# MSSRP-Temperature_System_beta.net
KiCad netlist of a schematic drawn in EAGLE
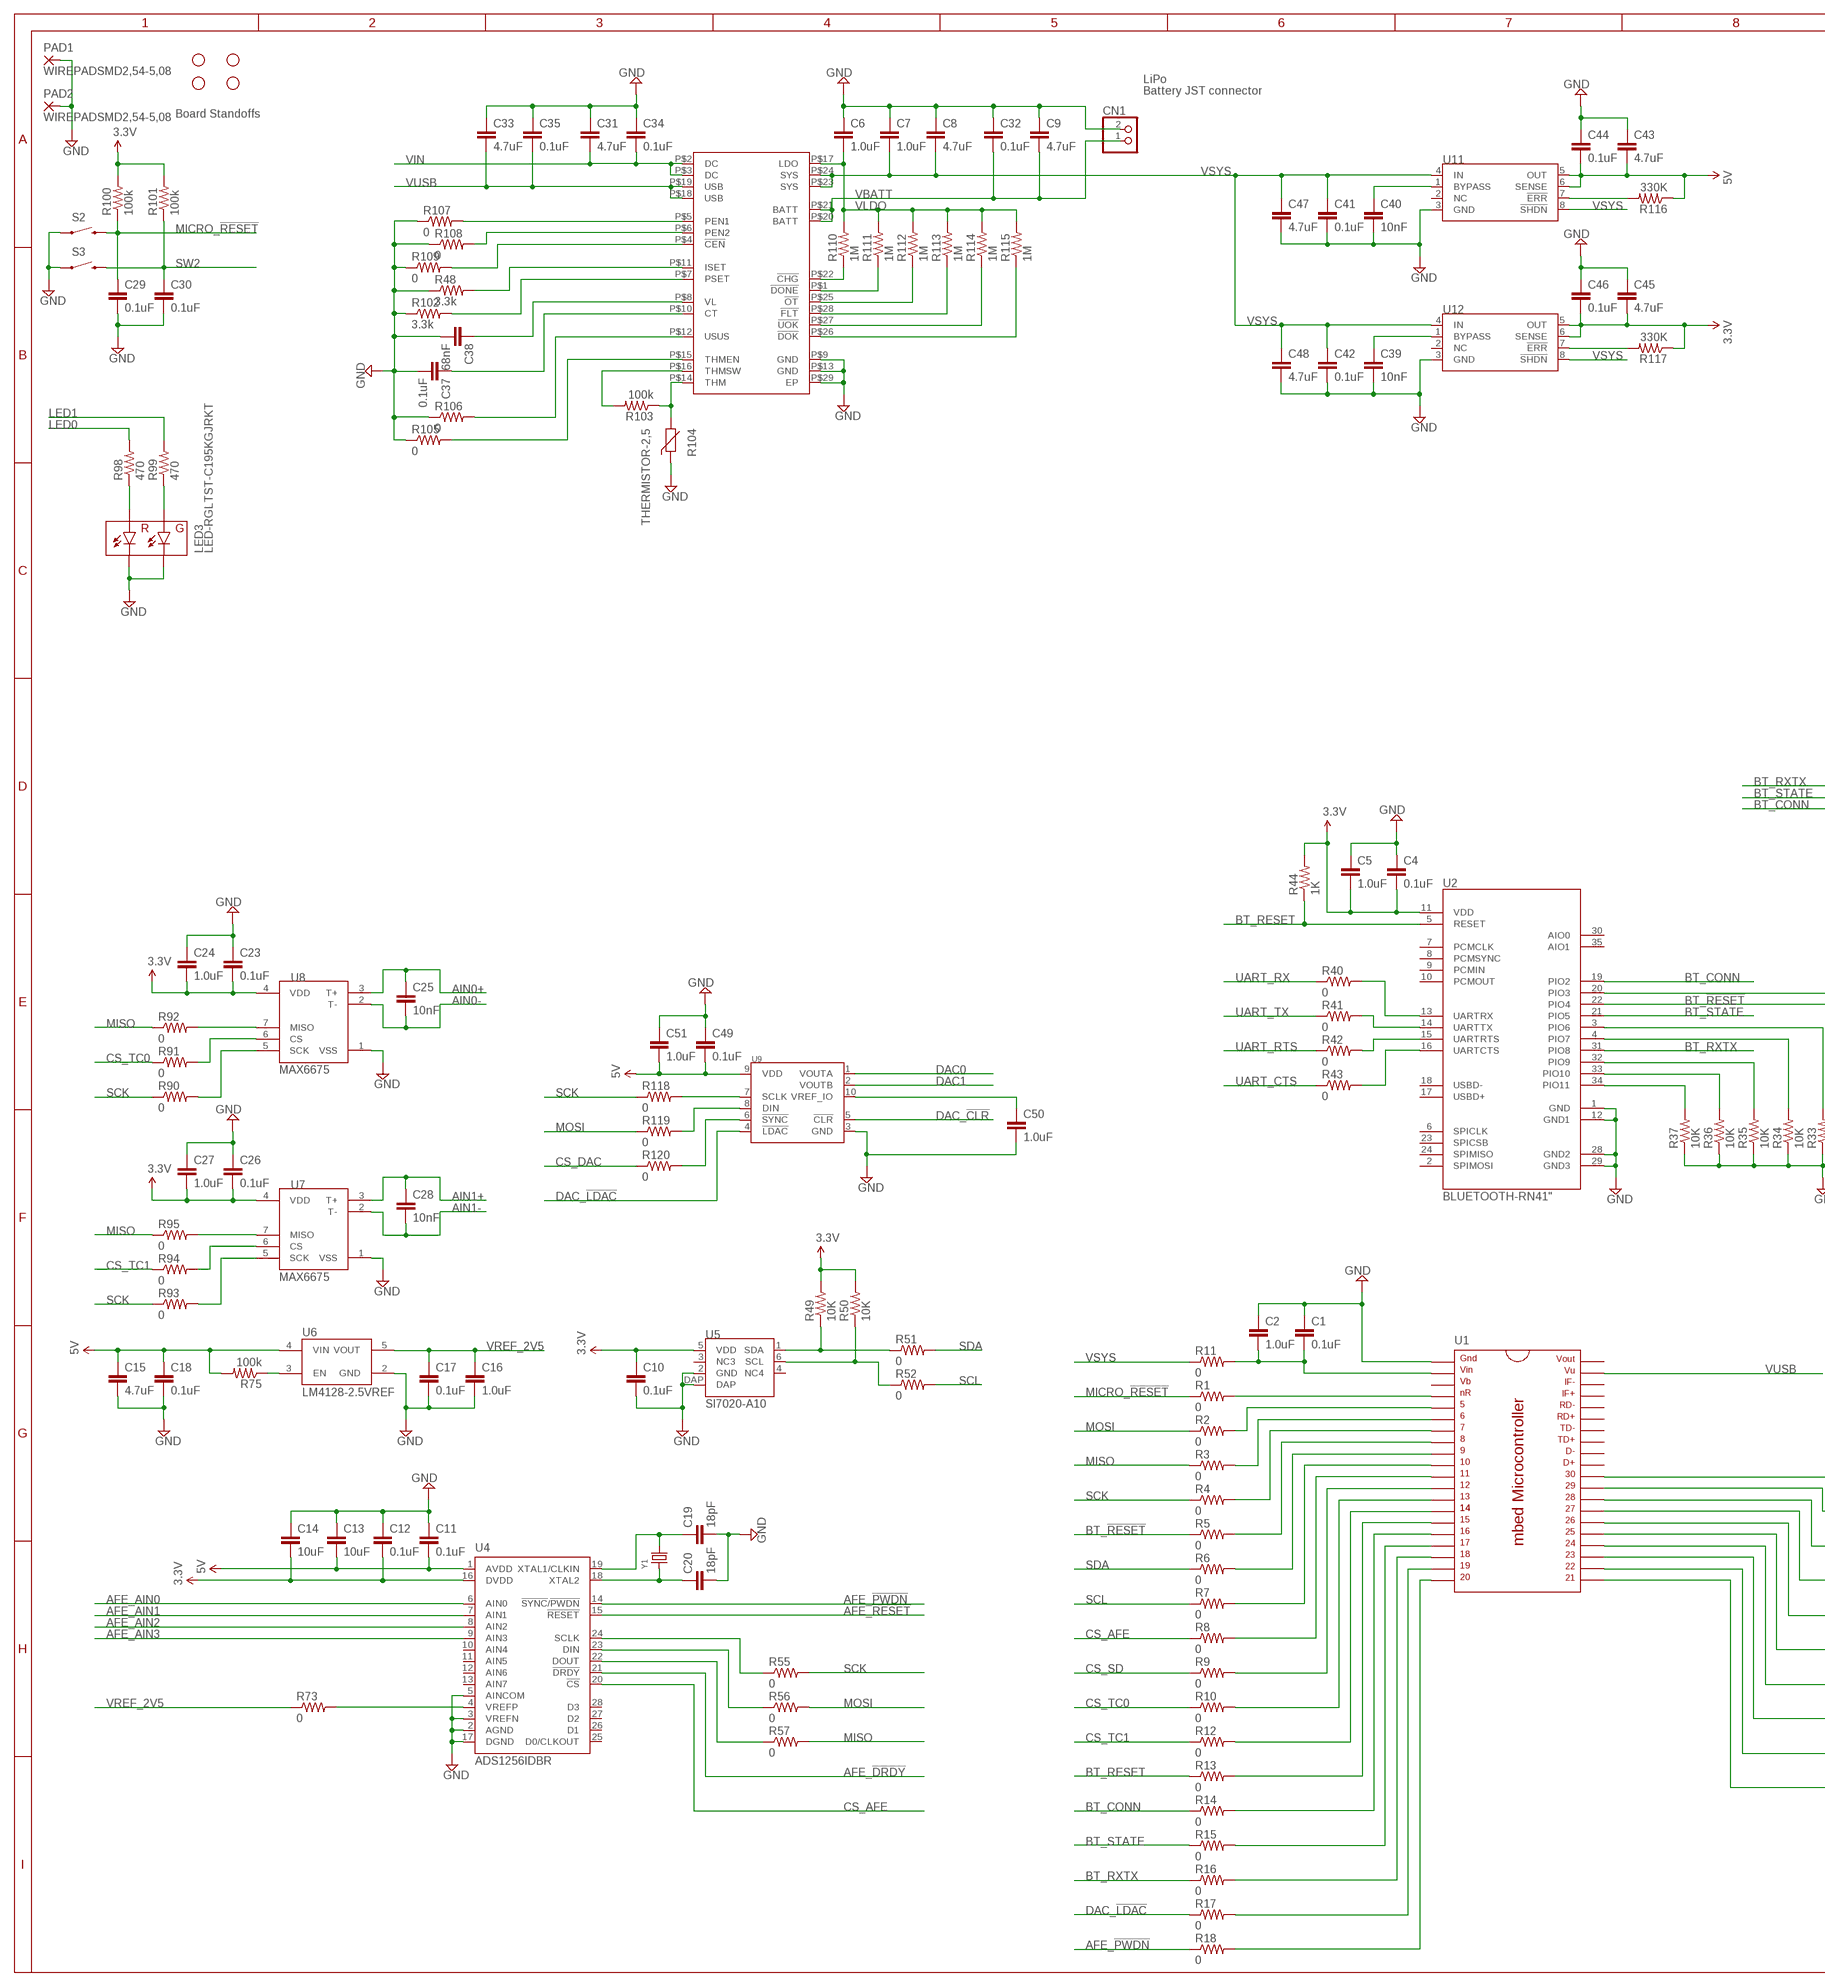
[diagram p0: schematic, sheet 1, part 1 of 2]
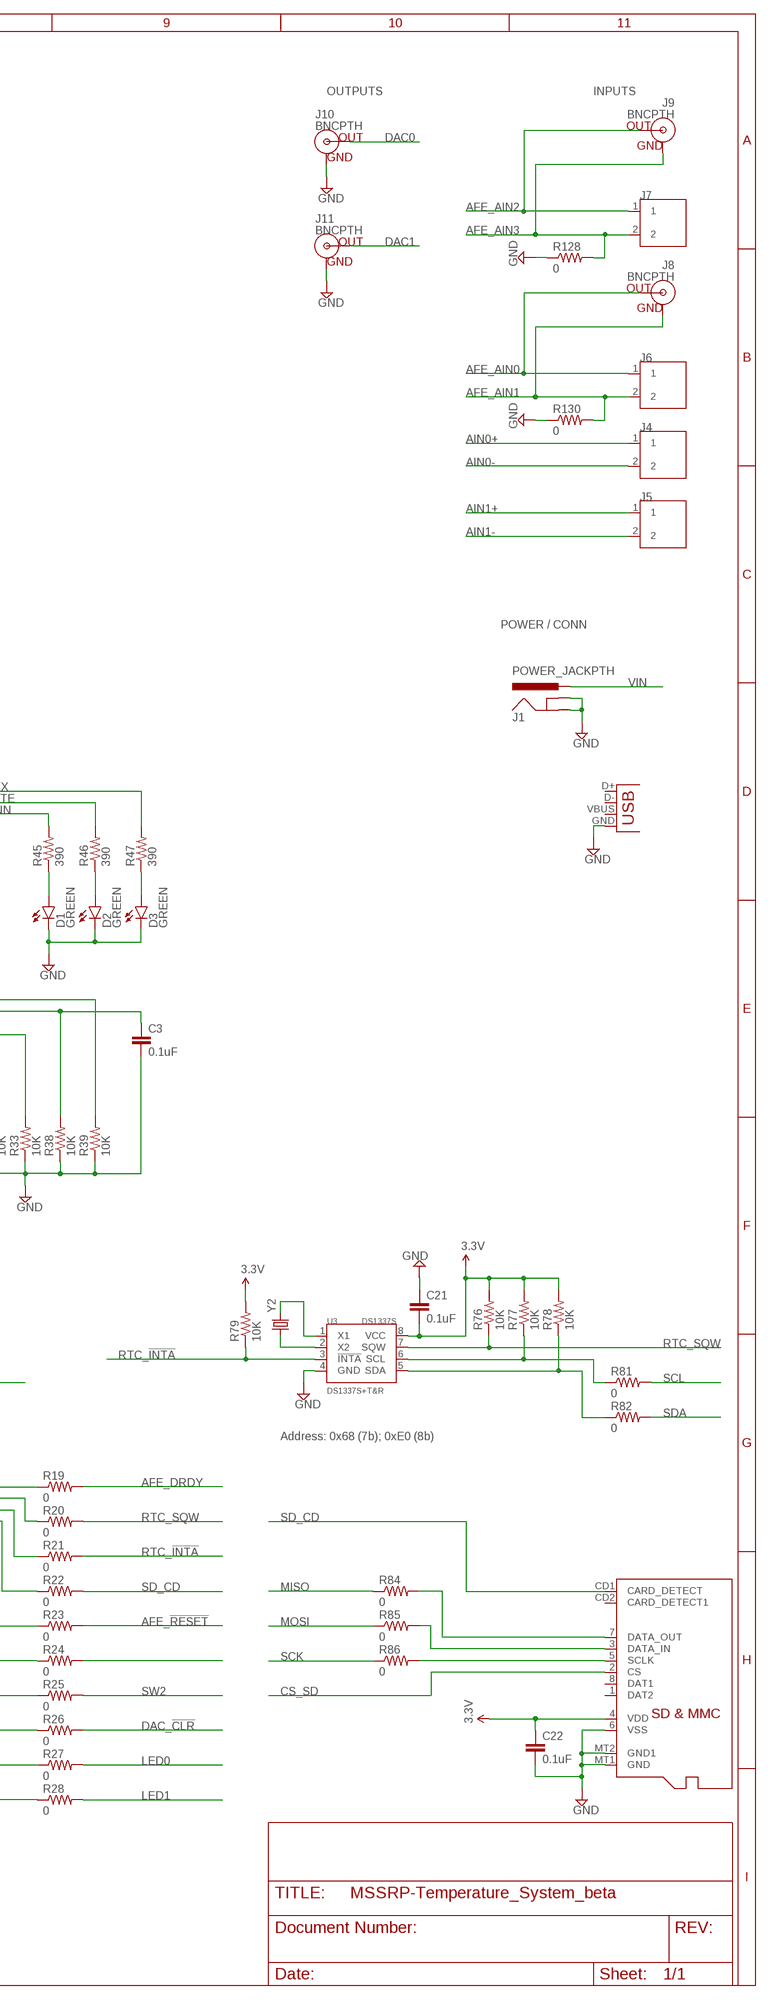
[diagram p1: schematic, sheet 1, part 2 of 2]

(export (version "E")
  (design (tool "Eeschema 10.0.6"))
  (components
    (comp (ref "C1")
      (value "0.1uF")
      (footprint "eagle-import:0603-CAP")
      (libsource (lib "eagle-import") (part "0.1UF-25V-5%(0603)"))
    )
    (comp (ref "C2")
      (value "1.0uF")
      (footprint "eagle-import:0603-CAP")
      (libsource (lib "eagle-import") (part "1.0UF-16V-10%(0603)"))
    )
    (comp (ref "C3")
      (value "0.1uF")
      (footprint "eagle-import:0603-CAP")
      (libsource (lib "eagle-import") (part "0.1UF-25V-5%(0603)"))
    )
    (comp (ref "C4")
      (value "0.1uF")
      (footprint "eagle-import:0603-CAP")
      (libsource (lib "eagle-import") (part "0.1UF-25V-5%(0603)"))
    )
    (comp (ref "C5")
      (value "1.0uF")
      (footprint "eagle-import:0603-CAP")
      (libsource (lib "eagle-import") (part "1.0UF-16V-10%(0603)"))
    )
    (comp (ref "C6")
      (value "1.0uF")
      (footprint "eagle-import:0603-CAP")
      (libsource (lib "eagle-import") (part "1.0UF-16V-10%(0603)"))
    )
    (comp (ref "C7")
      (value "1.0uF")
      (footprint "eagle-import:0603-CAP")
      (libsource (lib "eagle-import") (part "1.0UF-16V-10%(0603)"))
    )
    (comp (ref "C8")
      (value "4.7uF")
      (footprint "eagle-import:0603-CAP")
      (libsource (lib "eagle-import") (part "4.7UF-6.3V-10%(0603)0603"))
    )
    (comp (ref "C9")
      (value "4.7uF")
      (footprint "eagle-import:0603-CAP")
      (libsource (lib "eagle-import") (part "4.7UF-6.3V-10%(0603)0603"))
    )
    (comp (ref "C10")
      (value "0.1uF")
      (footprint "eagle-import:0603-CAP")
      (libsource (lib "eagle-import") (part "0.1UF-25V-5%(0603)"))
    )
    (comp (ref "C11")
      (value "0.1uF")
      (footprint "eagle-import:0603-CAP")
      (libsource (lib "eagle-import") (part "0.1UF-25V-5%(0603)"))
    )
    (comp (ref "C12")
      (value "0.1uF")
      (footprint "eagle-import:0603-CAP")
      (libsource (lib "eagle-import") (part "0.1UF-25V-5%(0603)"))
    )
    (comp (ref "C13")
      (value "10uF")
      (footprint "eagle-import:0603-CAP")
      (libsource (lib "eagle-import") (part "10UF-6.3V-20%(0603)"))
    )
    (comp (ref "C14")
      (value "10uF")
      (footprint "eagle-import:0603-CAP")
      (libsource (lib "eagle-import") (part "10UF-6.3V-20%(0603)"))
    )
    (comp (ref "C15")
      (value "4.7uF")
      (footprint "eagle-import:0603-CAP")
      (libsource (lib "eagle-import") (part "4.7UF-6.3V-10%(0603)0603"))
    )
    (comp (ref "C16")
      (value "1.0uF")
      (footprint "eagle-import:0603-CAP")
      (libsource (lib "eagle-import") (part "1.0UF-16V-10%(0603)"))
    )
    (comp (ref "C17")
      (value "0.1uF")
      (footprint "eagle-import:0603-CAP")
      (libsource (lib "eagle-import") (part "0.1UF-25V-5%(0603)"))
    )
    (comp (ref "C18")
      (value "0.1uF")
      (footprint "eagle-import:0603-CAP")
      (libsource (lib "eagle-import") (part "0.1UF-25V-5%(0603)"))
    )
    (comp (ref "C19")
      (value "18pF")
      (footprint "eagle-import:0603-CAP")
      (libsource (lib "eagle-import") (part "18PF-50V-5%(0603)"))
    )
    (comp (ref "C20")
      (value "18pF")
      (footprint "eagle-import:0603-CAP")
      (libsource (lib "eagle-import") (part "18PF-50V-5%(0603)"))
    )
    (comp (ref "C21")
      (value "0.1uF")
      (footprint "eagle-import:0603-CAP")
      (libsource (lib "eagle-import") (part "0.1UF-25V-5%(0603)"))
    )
    (comp (ref "C22")
      (value "0.1uF")
      (footprint "eagle-import:0603-CAP")
      (libsource (lib "eagle-import") (part "0.1UF-25V-5%(0603)"))
    )
    (comp (ref "C23")
      (value "0.1uF")
      (footprint "eagle-import:0603-CAP")
      (libsource (lib "eagle-import") (part "0.1UF-25V-5%(0603)"))
    )
    (comp (ref "C24")
      (value "1.0uF")
      (footprint "eagle-import:0603-CAP")
      (libsource (lib "eagle-import") (part "1.0UF-16V-10%(0603)"))
    )
    (comp (ref "C25")
      (value "10nF")
      (footprint "eagle-import:0603-CAP")
      (libsource (lib "eagle-import") (part "10NF/10000PF-50V-10%(0603)"))
    )
    (comp (ref "C26")
      (value "0.1uF")
      (footprint "eagle-import:0603-CAP")
      (libsource (lib "eagle-import") (part "0.1UF-25V-5%(0603)"))
    )
    (comp (ref "C27")
      (value "1.0uF")
      (footprint "eagle-import:0603-CAP")
      (libsource (lib "eagle-import") (part "1.0UF-16V-10%(0603)"))
    )
    (comp (ref "C28")
      (value "10nF")
      (footprint "eagle-import:0603-CAP")
      (libsource (lib "eagle-import") (part "10NF/10000PF-50V-10%(0603)"))
    )
    (comp (ref "C29")
      (value "0.1uF")
      (footprint "eagle-import:0603-CAP")
      (libsource (lib "eagle-import") (part "0.1UF-25V-5%(0603)"))
    )
    (comp (ref "C30")
      (value "0.1uF")
      (footprint "eagle-import:0603-CAP")
      (libsource (lib "eagle-import") (part "0.1UF-25V-5%(0603)"))
    )
    (comp (ref "C31")
      (value "4.7uF")
      (footprint "eagle-import:0603-CAP")
      (libsource (lib "eagle-import") (part "4.7UF-6.3V-10%(0603)0603"))
    )
    (comp (ref "C32")
      (value "0.1uF")
      (footprint "eagle-import:0603-CAP")
      (libsource (lib "eagle-import") (part "0.1UF-25V-5%(0603)"))
    )
    (comp (ref "C33")
      (value "4.7uF")
      (footprint "eagle-import:0603-CAP")
      (libsource (lib "eagle-import") (part "4.7UF-6.3V-10%(0603)0603"))
    )
    (comp (ref "C34")
      (value "0.1uF")
      (footprint "eagle-import:0603-CAP")
      (libsource (lib "eagle-import") (part "0.1UF-25V-5%(0603)"))
    )
    (comp (ref "C35")
      (value "0.1uF")
      (footprint "eagle-import:0603-CAP")
      (libsource (lib "eagle-import") (part "0.1UF-25V-5%(0603)"))
    )
    (comp (ref "C37")
      (value "0.1uF")
      (footprint "eagle-import:0603-CAP")
      (libsource (lib "eagle-import") (part "0.1UF-25V-5%(0603)"))
    )
    (comp (ref "C38")
      (value "68nF")
      (footprint "eagle-import:0603-CAP")
      (libsource (lib "eagle-import") (part "0.1UF-25V-5%(0603)"))
    )
    (comp (ref "C39")
      (value "10nF")
      (footprint "eagle-import:0603-CAP")
      (libsource (lib "eagle-import") (part "10NF/10000PF-50V-10%(0603)"))
    )
    (comp (ref "C40")
      (value "10nF")
      (footprint "eagle-import:0603-CAP")
      (libsource (lib "eagle-import") (part "10NF/10000PF-50V-10%(0603)"))
    )
    (comp (ref "C41")
      (value "0.1uF")
      (footprint "eagle-import:0603-CAP")
      (libsource (lib "eagle-import") (part "0.1UF-25V-5%(0603)"))
    )
    (comp (ref "C42")
      (value "0.1uF")
      (footprint "eagle-import:0603-CAP")
      (libsource (lib "eagle-import") (part "0.1UF-25V-5%(0603)"))
    )
    (comp (ref "C43")
      (value "4.7uF")
      (footprint "eagle-import:0603-CAP")
      (libsource (lib "eagle-import") (part "4.7UF-6.3V-10%(0603)0603"))
    )
    (comp (ref "C44")
      (value "0.1uF")
      (footprint "eagle-import:0603-CAP")
      (libsource (lib "eagle-import") (part "0.1UF-25V-5%(0603)"))
    )
    (comp (ref "C45")
      (value "4.7uF")
      (footprint "eagle-import:0603-CAP")
      (libsource (lib "eagle-import") (part "4.7UF-6.3V-10%(0603)0603"))
    )
    (comp (ref "C46")
      (value "0.1uF")
      (footprint "eagle-import:0603-CAP")
      (libsource (lib "eagle-import") (part "0.1UF-25V-5%(0603)"))
    )
    (comp (ref "C47")
      (value "4.7uF")
      (footprint "eagle-import:0603-CAP")
      (libsource (lib "eagle-import") (part "4.7UF-6.3V-10%(0603)0603"))
    )
    (comp (ref "C48")
      (value "4.7uF")
      (footprint "eagle-import:0603-CAP")
      (libsource (lib "eagle-import") (part "4.7UF-6.3V-10%(0603)0603"))
    )
    (comp (ref "C49")
      (value "0.1uF")
      (footprint "eagle-import:0603-CAP")
      (libsource (lib "eagle-import") (part "0.1UF-25V-5%(0603)"))
    )
    (comp (ref "C50")
      (value "1.0uF")
      (footprint "eagle-import:0603-CAP")
      (libsource (lib "eagle-import") (part "1.0UF-16V-10%(0603)"))
    )
    (comp (ref "C51")
      (value "1.0uF")
      (footprint "eagle-import:0603-CAP")
      (libsource (lib "eagle-import") (part "1.0UF-16V-10%(0603)"))
    )
    (comp (ref "CN1")
      (value "JST_2PIN-THM-RA")
      (footprint "eagle-import:JST-PH-2-THM-RA")
      (libsource (lib "eagle-import") (part "JST_2PIN-THM-RA"))
    )
    (comp (ref "D1")
      (value "GREEN")
      (footprint "eagle-import:LED-0603")
      (libsource (lib "eagle-import") (part "LED-GREEN0603"))
    )
    (comp (ref "D2")
      (value "GREEN")
      (footprint "eagle-import:LED-0603")
      (libsource (lib "eagle-import") (part "LED-GREEN0603"))
    )
    (comp (ref "D3")
      (value "GREEN")
      (footprint "eagle-import:LED-0603")
      (libsource (lib "eagle-import") (part "LED-GREEN0603"))
    )
    (comp (ref "J1")
      (value "POWER_JACKPTH")
      (footprint "eagle-import:POWER_JACK_PTH")
      (libsource (lib "eagle-import") (part "POWER_JACKPTH"))
    )
    (comp (ref "J2")
      (value "USBSMD")
      (footprint "eagle-import:USB-MINIB")
      (libsource (lib "eagle-import") (part "USBSMD"))
    )
    (comp (ref "J4")
      (value "TE-2-TERMBLOCK")
      (footprint "eagle-import:TE-2-TERMBLOCK")
      (libsource (lib "eagle-import") (part "TE-2-TERMBLOCK"))
    )
    (comp (ref "J5")
      (value "TE-2-TERMBLOCK")
      (footprint "eagle-import:TE-2-TERMBLOCK")
      (libsource (lib "eagle-import") (part "TE-2-TERMBLOCK"))
    )
    (comp (ref "J6")
      (value "TE-2-TERMBLOCK")
      (footprint "eagle-import:TE-2-TERMBLOCK")
      (libsource (lib "eagle-import") (part "TE-2-TERMBLOCK"))
    )
    (comp (ref "J7")
      (value "TE-2-TERMBLOCK")
      (footprint "eagle-import:TE-2-TERMBLOCK")
      (libsource (lib "eagle-import") (part "TE-2-TERMBLOCK"))
    )
    (comp (ref "J8")
      (value "BNCPTH")
      (footprint "eagle-import:BNC")
      (libsource (lib "eagle-import") (part "BNCPTH"))
    )
    (comp (ref "J9")
      (value "BNCPTH")
      (footprint "eagle-import:BNC")
      (libsource (lib "eagle-import") (part "BNCPTH"))
    )
    (comp (ref "J10")
      (value "BNCPTH")
      (footprint "eagle-import:BNC")
      (libsource (lib "eagle-import") (part "BNCPTH"))
    )
    (comp (ref "J11")
      (value "BNCPTH")
      (footprint "eagle-import:BNC")
      (libsource (lib "eagle-import") (part "BNCPTH"))
    )
    (comp (ref "LED3")
      (value "LED-RGLTST-C195KGJRKT")
      (footprint "eagle-import:LTST-C195KGJRKT")
      (libsource (lib "eagle-import") (part "LED-RGLTST-C195KGJRKT"))
    )
    (comp (ref "PAD1")
      (value "WIREPADSMD2,54-5,08")
      (footprint "eagle-import:SMD2,54-5,08")
      (libsource (lib "eagle-import") (part "WIREPADSMD2,54-5,08"))
    )
    (comp (ref "PAD2")
      (value "WIREPADSMD2,54-5,08")
      (footprint "eagle-import:SMD2,54-5,08")
      (libsource (lib "eagle-import") (part "WIREPADSMD2,54-5,08"))
    )
    (comp (ref "R1")
      (value "0")
      (footprint "eagle-import:0603")
      (libsource (lib "eagle-import") (part "0OHM1/10W5%(0603)"))
    )
    (comp (ref "R2")
      (value "0")
      (footprint "eagle-import:0603")
      (libsource (lib "eagle-import") (part "0OHM1/10W5%(0603)"))
    )
    (comp (ref "R3")
      (value "0")
      (footprint "eagle-import:0603")
      (libsource (lib "eagle-import") (part "0OHM1/10W5%(0603)"))
    )
    (comp (ref "R4")
      (value "0")
      (footprint "eagle-import:0603")
      (libsource (lib "eagle-import") (part "0OHM1/10W5%(0603)"))
    )
    (comp (ref "R5")
      (value "0")
      (footprint "eagle-import:0603")
      (libsource (lib "eagle-import") (part "0OHM1/10W5%(0603)"))
    )
    (comp (ref "R6")
      (value "0")
      (footprint "eagle-import:0603")
      (libsource (lib "eagle-import") (part "0OHM1/10W5%(0603)"))
    )
    (comp (ref "R7")
      (value "0")
      (footprint "eagle-import:0603")
      (libsource (lib "eagle-import") (part "0OHM1/10W5%(0603)"))
    )
    (comp (ref "R8")
      (value "0")
      (footprint "eagle-import:0603")
      (libsource (lib "eagle-import") (part "0OHM1/10W5%(0603)"))
    )
    (comp (ref "R9")
      (value "0")
      (footprint "eagle-import:0603")
      (libsource (lib "eagle-import") (part "0OHM1/10W5%(0603)"))
    )
    (comp (ref "R10")
      (value "0")
      (footprint "eagle-import:0603")
      (libsource (lib "eagle-import") (part "0OHM1/10W5%(0603)"))
    )
    (comp (ref "R11")
      (value "0")
      (footprint "eagle-import:0603")
      (libsource (lib "eagle-import") (part "0OHM1/10W5%(0603)"))
    )
    (comp (ref "R12")
      (value "0")
      (footprint "eagle-import:0603")
      (libsource (lib "eagle-import") (part "0OHM1/10W5%(0603)"))
    )
    (comp (ref "R13")
      (value "0")
      (footprint "eagle-import:0603")
      (libsource (lib "eagle-import") (part "0OHM1/10W5%(0603)"))
    )
    (comp (ref "R14")
      (value "0")
      (footprint "eagle-import:0603")
      (libsource (lib "eagle-import") (part "0OHM1/10W5%(0603)"))
    )
    (comp (ref "R15")
      (value "0")
      (footprint "eagle-import:0603")
      (libsource (lib "eagle-import") (part "0OHM1/10W5%(0603)"))
    )
    (comp (ref "R16")
      (value "0")
      (footprint "eagle-import:0603")
      (libsource (lib "eagle-import") (part "0OHM1/10W5%(0603)"))
    )
    (comp (ref "R17")
      (value "0")
      (footprint "eagle-import:0603")
      (libsource (lib "eagle-import") (part "0OHM1/10W5%(0603)"))
    )
    (comp (ref "R18")
      (value "0")
      (footprint "eagle-import:0603")
      (libsource (lib "eagle-import") (part "0OHM1/10W5%(0603)"))
    )
    (comp (ref "R19")
      (value "0")
      (footprint "eagle-import:0603")
      (libsource (lib "eagle-import") (part "0OHM1/10W5%(0603)"))
    )
    (comp (ref "R20")
      (value "0")
      (footprint "eagle-import:0603")
      (libsource (lib "eagle-import") (part "0OHM1/10W5%(0603)"))
    )
    (comp (ref "R21")
      (value "0")
      (footprint "eagle-import:0603")
      (libsource (lib "eagle-import") (part "0OHM1/10W5%(0603)"))
    )
    (comp (ref "R22")
      (value "0")
      (footprint "eagle-import:0603")
      (libsource (lib "eagle-import") (part "0OHM1/10W5%(0603)"))
    )
    (comp (ref "R23")
      (value "0")
      (footprint "eagle-import:0603")
      (libsource (lib "eagle-import") (part "0OHM1/10W5%(0603)"))
    )
    (comp (ref "R24")
      (value "0")
      (footprint "eagle-import:0603")
      (libsource (lib "eagle-import") (part "0OHM1/10W5%(0603)"))
    )
    (comp (ref "R25")
      (value "0")
      (footprint "eagle-import:0603")
      (libsource (lib "eagle-import") (part "0OHM1/10W5%(0603)"))
    )
    (comp (ref "R26")
      (value "0")
      (footprint "eagle-import:0603")
      (libsource (lib "eagle-import") (part "0OHM1/10W5%(0603)"))
    )
    (comp (ref "R27")
      (value "0")
      (footprint "eagle-import:0603")
      (libsource (lib "eagle-import") (part "0OHM1/10W5%(0603)"))
    )
    (comp (ref "R28")
      (value "0")
      (footprint "eagle-import:0603")
      (libsource (lib "eagle-import") (part "0OHM1/10W5%(0603)"))
    )
    (comp (ref "R33")
      (value "10K")
      (footprint "eagle-import:0603-RES")
      (libsource (lib "eagle-import") (part "10KOHM1/10W1%(0603)0603"))
    )
    (comp (ref "R34")
      (value "10K")
      (footprint "eagle-import:0603-RES")
      (libsource (lib "eagle-import") (part "10KOHM1/10W1%(0603)0603"))
    )
    (comp (ref "R35")
      (value "10K")
      (footprint "eagle-import:0603-RES")
      (libsource (lib "eagle-import") (part "10KOHM1/10W1%(0603)0603"))
    )
    (comp (ref "R36")
      (value "10K")
      (footprint "eagle-import:0603-RES")
      (libsource (lib "eagle-import") (part "10KOHM1/10W1%(0603)0603"))
    )
    (comp (ref "R37")
      (value "10K")
      (footprint "eagle-import:0603-RES")
      (libsource (lib "eagle-import") (part "10KOHM1/10W1%(0603)0603"))
    )
    (comp (ref "R38")
      (value "10K")
      (footprint "eagle-import:0603-RES")
      (libsource (lib "eagle-import") (part "10KOHM1/10W1%(0603)0603"))
    )
    (comp (ref "R39")
      (value "10K")
      (footprint "eagle-import:0603-RES")
      (libsource (lib "eagle-import") (part "10KOHM1/10W1%(0603)0603"))
    )
    (comp (ref "R40")
      (value "0")
      (footprint "eagle-import:0603")
      (libsource (lib "eagle-import") (part "0OHM1/10W5%(0603)"))
    )
    (comp (ref "R41")
      (value "0")
      (footprint "eagle-import:0603")
      (libsource (lib "eagle-import") (part "0OHM1/10W5%(0603)"))
    )
    (comp (ref "R42")
      (value "0")
      (footprint "eagle-import:0603")
      (libsource (lib "eagle-import") (part "0OHM1/10W5%(0603)"))
    )
    (comp (ref "R43")
      (value "0")
      (footprint "eagle-import:0603")
      (libsource (lib "eagle-import") (part "0OHM1/10W5%(0603)"))
    )
    (comp (ref "R44")
      (value "1K")
      (footprint "eagle-import:0603-RES")
      (libsource (lib "eagle-import") (part "1KOHM1/10W1%(0603)"))
    )
    (comp (ref "R45")
      (value "390")
      (footprint "eagle-import:0603-RES")
      (libsource (lib "eagle-import") (part "390OHM1/10W1%(0603)"))
    )
    (comp (ref "R46")
      (value "390")
      (footprint "eagle-import:0603-RES")
      (libsource (lib "eagle-import") (part "390OHM1/10W1%(0603)"))
    )
    (comp (ref "R47")
      (value "390")
      (footprint "eagle-import:0603-RES")
      (libsource (lib "eagle-import") (part "390OHM1/10W1%(0603)"))
    )
    (comp (ref "R48")
      (value "3.3k")
      (footprint "eagle-import:0603-RES")
      (libsource (lib "eagle-import") (part "3.3MOHM-1/10W-1%(0603)"))
    )
    (comp (ref "R49")
      (value "10K")
      (footprint "eagle-import:0603-RES")
      (libsource (lib "eagle-import") (part "10KOHM1/10W1%(0603)0603"))
    )
    (comp (ref "R50")
      (value "10K")
      (footprint "eagle-import:0603-RES")
      (libsource (lib "eagle-import") (part "10KOHM1/10W1%(0603)0603"))
    )
    (comp (ref "R51")
      (value "0")
      (footprint "eagle-import:0603")
      (libsource (lib "eagle-import") (part "0OHM1/10W5%(0603)"))
    )
    (comp (ref "R52")
      (value "0")
      (footprint "eagle-import:0603")
      (libsource (lib "eagle-import") (part "0OHM1/10W5%(0603)"))
    )
    (comp (ref "R55")
      (value "0")
      (footprint "eagle-import:0603")
      (libsource (lib "eagle-import") (part "0OHM1/10W5%(0603)"))
    )
    (comp (ref "R56")
      (value "0")
      (footprint "eagle-import:0603")
      (libsource (lib "eagle-import") (part "0OHM1/10W5%(0603)"))
    )
    (comp (ref "R57")
      (value "0")
      (footprint "eagle-import:0603")
      (libsource (lib "eagle-import") (part "0OHM1/10W5%(0603)"))
    )
    (comp (ref "R73")
      (value "0")
      (footprint "eagle-import:0603")
      (libsource (lib "eagle-import") (part "0OHM1/10W5%(0603)"))
    )
    (comp (ref "R75")
      (value "100k")
      (footprint "eagle-import:0603-RES")
      (libsource (lib "eagle-import") (part "100KOHM1/10W1%(0603)"))
    )
    (comp (ref "R76")
      (value "10K")
      (footprint "eagle-import:0603-RES")
      (libsource (lib "eagle-import") (part "10KOHM1/10W1%(0603)0603"))
    )
    (comp (ref "R77")
      (value "10K")
      (footprint "eagle-import:0603-RES")
      (libsource (lib "eagle-import") (part "10KOHM1/10W1%(0603)0603"))
    )
    (comp (ref "R78")
      (value "10K")
      (footprint "eagle-import:0603-RES")
      (libsource (lib "eagle-import") (part "10KOHM1/10W1%(0603)0603"))
    )
    (comp (ref "R79")
      (value "10K")
      (footprint "eagle-import:0603-RES")
      (libsource (lib "eagle-import") (part "10KOHM1/10W1%(0603)0603"))
    )
    (comp (ref "R81")
      (value "0")
      (footprint "eagle-import:0603")
      (libsource (lib "eagle-import") (part "0OHM1/10W5%(0603)"))
    )
    (comp (ref "R82")
      (value "0")
      (footprint "eagle-import:0603")
      (libsource (lib "eagle-import") (part "0OHM1/10W5%(0603)"))
    )
    (comp (ref "R84")
      (value "0")
      (footprint "eagle-import:0603")
      (libsource (lib "eagle-import") (part "0OHM1/10W5%(0603)"))
    )
    (comp (ref "R85")
      (value "0")
      (footprint "eagle-import:0603")
      (libsource (lib "eagle-import") (part "0OHM1/10W5%(0603)"))
    )
    (comp (ref "R86")
      (value "0")
      (footprint "eagle-import:0603")
      (libsource (lib "eagle-import") (part "0OHM1/10W5%(0603)"))
    )
    (comp (ref "R90")
      (value "0")
      (footprint "eagle-import:0603")
      (libsource (lib "eagle-import") (part "0OHM1/10W5%(0603)"))
    )
    (comp (ref "R91")
      (value "0")
      (footprint "eagle-import:0603")
      (libsource (lib "eagle-import") (part "0OHM1/10W5%(0603)"))
    )
    (comp (ref "R92")
      (value "0")
      (footprint "eagle-import:0603")
      (libsource (lib "eagle-import") (part "0OHM1/10W5%(0603)"))
    )
    (comp (ref "R93")
      (value "0")
      (footprint "eagle-import:0603")
      (libsource (lib "eagle-import") (part "0OHM1/10W5%(0603)"))
    )
    (comp (ref "R94")
      (value "0")
      (footprint "eagle-import:0603")
      (libsource (lib "eagle-import") (part "0OHM1/10W5%(0603)"))
    )
    (comp (ref "R95")
      (value "0")
      (footprint "eagle-import:0603")
      (libsource (lib "eagle-import") (part "0OHM1/10W5%(0603)"))
    )
    (comp (ref "R98")
      (value "470")
      (footprint "eagle-import:0603-RES")
      (libsource (lib "eagle-import") (part "470OHM1/10W1%(0603)"))
    )
    (comp (ref "R99")
      (value "470")
      (footprint "eagle-import:0603-RES")
      (libsource (lib "eagle-import") (part "470OHM1/10W1%(0603)"))
    )
    (comp (ref "R100")
      (value "100k")
      (footprint "eagle-import:0603-RES")
      (libsource (lib "eagle-import") (part "100KOHM1/10W1%(0603)"))
    )
    (comp (ref "R101")
      (value "100k")
      (footprint "eagle-import:0603-RES")
      (libsource (lib "eagle-import") (part "100KOHM1/10W1%(0603)"))
    )
    (comp (ref "R102")
      (value "3.3k")
      (footprint "eagle-import:0603-RES")
      (libsource (lib "eagle-import") (part "3.3MOHM-1/10W-1%(0603)"))
    )
    (comp (ref "R103")
      (value "100k")
      (footprint "eagle-import:0603-RES")
      (libsource (lib "eagle-import") (part "100OHM1/10W1%(0603)"))
    )
    (comp (ref "R104")
      (value "THERMISTOR-2,5")
      (footprint "eagle-import:RS-2,5")
      (libsource (lib "eagle-import") (part "THERMISTOR-2,5"))
    )
    (comp (ref "R105")
      (value "0")
      (footprint "eagle-import:0603")
      (libsource (lib "eagle-import") (part "0OHM1/10W5%(0603)"))
    )
    (comp (ref "R106")
      (value "0")
      (footprint "eagle-import:0603")
      (libsource (lib "eagle-import") (part "0OHM1/10W5%(0603)"))
    )
    (comp (ref "R107")
      (value "0")
      (footprint "eagle-import:0603")
      (libsource (lib "eagle-import") (part "0OHM1/10W5%(0603)"))
    )
    (comp (ref "R108")
      (value "0")
      (footprint "eagle-import:0603")
      (libsource (lib "eagle-import") (part "0OHM1/10W5%(0603)"))
    )
    (comp (ref "R109")
      (value "0")
      (footprint "eagle-import:0603")
      (libsource (lib "eagle-import") (part "0OHM1/10W5%(0603)"))
    )
    (comp (ref "R110")
      (value "1M")
      (footprint "eagle-import:0603-RES")
      (libsource (lib "eagle-import") (part "330KOHM1/10W1%(0603)0603"))
    )
    (comp (ref "R111")
      (value "1M")
      (footprint "eagle-import:0603-RES")
      (libsource (lib "eagle-import") (part "330KOHM1/10W1%(0603)0603"))
    )
    (comp (ref "R112")
      (value "1M")
      (footprint "eagle-import:0603-RES")
      (libsource (lib "eagle-import") (part "330KOHM1/10W1%(0603)0603"))
    )
    (comp (ref "R113")
      (value "1M")
      (footprint "eagle-import:0603-RES")
      (libsource (lib "eagle-import") (part "330KOHM1/10W1%(0603)0603"))
    )
    (comp (ref "R114")
      (value "1M")
      (footprint "eagle-import:0603-RES")
      (libsource (lib "eagle-import") (part "330KOHM1/10W1%(0603)0603"))
    )
    (comp (ref "R115")
      (value "1M")
      (footprint "eagle-import:0603-RES")
      (libsource (lib "eagle-import") (part "330KOHM1/10W1%(0603)0603"))
    )
    (comp (ref "R116")
      (value "330K")
      (footprint "eagle-import:0603-RES")
      (libsource (lib "eagle-import") (part "330KOHM1/10W1%(0603)0603"))
    )
    (comp (ref "R117")
      (value "330K")
      (footprint "eagle-import:0603-RES")
      (libsource (lib "eagle-import") (part "330KOHM1/10W1%(0603)0603"))
    )
    (comp (ref "R118")
      (value "0")
      (footprint "eagle-import:0603")
      (libsource (lib "eagle-import") (part "0OHM1/10W5%(0603)"))
    )
    (comp (ref "R119")
      (value "0")
      (footprint "eagle-import:0603")
      (libsource (lib "eagle-import") (part "0OHM1/10W5%(0603)"))
    )
    (comp (ref "R120")
      (value "0")
      (footprint "eagle-import:0603")
      (libsource (lib "eagle-import") (part "0OHM1/10W5%(0603)"))
    )
    (comp (ref "R128")
      (value "0")
      (footprint "eagle-import:0603")
      (libsource (lib "eagle-import") (part "0OHM1/10W5%(0603)"))
    )
    (comp (ref "R130")
      (value "0")
      (footprint "eagle-import:0603")
      (libsource (lib "eagle-import") (part "0OHM1/10W5%(0603)"))
    )
    (comp (ref "S2")
      (value "SWITCH-MOMENTARY-2-SMD-1101NE")
      (footprint "eagle-import:TACTILE-SWITCH-1101NE")
      (libsource (lib "eagle-import") (part "SWITCH-MOMENTARY-2-SMD-1101NE"))
    )
    (comp (ref "S3")
      (value "SWITCH-MOMENTARY-2-SMD-1101NE")
      (footprint "eagle-import:TACTILE-SWITCH-1101NE")
      (libsource (lib "eagle-import") (part "SWITCH-MOMENTARY-2-SMD-1101NE"))
    )
    (comp (ref "STANDOFF1")
      (value "STAND-OFF")
      (footprint "eagle-import:STAND-OFF")
      (libsource (lib "eagle-import") (part "STAND-OFF"))
    )
    (comp (ref "STANDOFF2")
      (value "STAND-OFF")
      (footprint "eagle-import:STAND-OFF")
      (libsource (lib "eagle-import") (part "STAND-OFF"))
    )
    (comp (ref "STANDOFF3")
      (value "STAND-OFF")
      (footprint "eagle-import:STAND-OFF")
      (libsource (lib "eagle-import") (part "STAND-OFF"))
    )
    (comp (ref "STANDOFF4")
      (value "STAND-OFF")
      (footprint "eagle-import:STAND-OFF")
      (libsource (lib "eagle-import") (part "STAND-OFF"))
    )
    (comp (ref "U$1")
      (value "MICROSD")
      (footprint "eagle-import:MICROSD")
      (libsource (lib "eagle-import") (part "MICROSD"))
    )
    (comp (ref "U1")
      (value "MBED")
      (footprint "eagle-import:DIL40_0.9")
      (libsource (lib "eagle-import") (part "MBED"))
    )
    (comp (ref "U2")
      (value "BLUETOOTH-RN41\"")
      (footprint "eagle-import:RN41")
      (libsource (lib "eagle-import") (part "BLUETOOTH-RN41{dblquote}"))
    )
    (comp (ref "U3")
      (value "DS1337S+T&R")
      (footprint "eagle-import:SOIC8")
      (libsource (lib "eagle-import") (part "DS1337S+T&R"))
    )
    (comp (ref "U4")
      (value "ADS1256IDBR")
      (footprint "eagle-import:SSOP28")
      (libsource (lib "eagle-import") (part "ADS1256IDBR"))
    )
    (comp (ref "U5")
      (value "SI7020-A10")
      (footprint "eagle-import:DFN6")
      (libsource (lib "eagle-import") (part "SI7020-A10"))
    )
    (comp (ref "U6")
      (value "LM4128-2.5VREF")
      (footprint "eagle-import:SOT23-5")
      (libsource (lib "eagle-import") (part "LM4128-2.5VREF"))
    )
    (comp (ref "U7")
      (value "MAX6675")
      (footprint "eagle-import:SO08-MAX6675")
      (libsource (lib "eagle-import") (part "MAX6675"))
    )
    (comp (ref "U8")
      (value "MAX6675")
      (footprint "eagle-import:SO08-MAX6675")
      (libsource (lib "eagle-import") (part "MAX6675"))
    )
    (comp (ref "U9")
      (value "DAC7562")
      (footprint "eagle-import:MSOP10")
      (libsource (lib "eagle-import") (part "DAC7562"))
    )
    (comp (ref "U10")
      (value "MAX8934A")
      (footprint "eagle-import:QFN28")
      (libsource (lib "eagle-import") (part "MAX8934A"))
    )
    (comp (ref "U11")
      (value "LP2989AIM")
      (footprint "eagle-import:SOIC8")
      (libsource (lib "eagle-import") (part "LP2989AIM"))
    )
    (comp (ref "U12")
      (value "LP2989AIM")
      (footprint "eagle-import:SOIC8")
      (libsource (lib "eagle-import") (part "LP2989AIM"))
    )
    (comp (ref "Y1")
      (value "CRYSTALSMD")
      (footprint "eagle-import:HC49UP")
      (libsource (lib "eagle-import") (part "microbuilder_CRYSTALSMD"))
    )
    (comp (ref "Y2")
      (value "CRYSTALSMD")
      (footprint "eagle-import:HC49UP")
      (libsource (lib "eagle-import") (part "CRYSTALSMD"))
    )
  )
  (nets
    (net (code "1") (name "/AFE_AIN0") (class "Default")
      (node (ref "J6") (pin "1") (pinfunction "1_1") (pintype "passive"))
      (node (ref "J8") (pin "S") (pinfunction "OUT_S") (pintype "bidirectional"))
      (node (ref "U4") (pin "6") (pinfunction "AIN0_6") (pintype "input"))
    )
    (net (code "2") (name "/AFE_AIN1") (class "Default")
      (node (ref "J6") (pin "2") (pinfunction "2_2") (pintype "passive"))
      (node (ref "J8") (pin "GND") (pinfunction "GND_GND") (pintype "bidirectional"))
      (node (ref "R130") (pin "2") (pinfunction "2_2") (pintype "passive"))
      (node (ref "U4") (pin "7") (pinfunction "AIN1_7") (pintype "input"))
    )
    (net (code "3") (name "/AFE_AIN2") (class "Default")
      (node (ref "J7") (pin "1") (pinfunction "1_1") (pintype "passive"))
      (node (ref "J9") (pin "S") (pinfunction "OUT_S") (pintype "bidirectional"))
      (node (ref "U4") (pin "8") (pinfunction "AIN2_8") (pintype "input"))
    )
    (net (code "4") (name "/AFE_AIN3") (class "Default")
      (node (ref "J7") (pin "2") (pinfunction "2_2") (pintype "passive"))
      (node (ref "J9") (pin "GND") (pinfunction "GND_GND") (pintype "bidirectional"))
      (node (ref "R128") (pin "2") (pinfunction "2_2") (pintype "passive"))
      (node (ref "U4") (pin "9") (pinfunction "AIN3_9") (pintype "input"))
    )
    (net (code "5") (name "/AFE_DRDY") (class "Default")
      (node (ref "R19") (pin "2") (pinfunction "2_2") (pintype "passive"))
    )
    (net (code "6") (name "/AFE_~{DRDY}") (class "Default")
      (node (ref "U4") (pin "21") (pinfunction "~{DRDY}_21") (pintype "output"))
    )
    (net (code "7") (name "/AFE_~{PWDN}") (class "Default")
      (node (ref "R18") (pin "1") (pinfunction "1_1") (pintype "passive"))
      (node (ref "U4") (pin "14") (pinfunction "~{SYNC}/~{PWDN}_14") (pintype "input"))
    )
    (net (code "8") (name "/AFE_~{RESET}") (class "Default")
      (node (ref "R23") (pin "2") (pinfunction "2_2") (pintype "passive"))
      (node (ref "U4") (pin "15") (pinfunction "~{RESET}_15") (pintype "input"))
    )
    (net (code "9") (name "/AIN0+") (class "Default")
      (node (ref "C25") (pin "1") (pinfunction "1_1") (pintype "passive"))
      (node (ref "J4") (pin "1") (pinfunction "1_1") (pintype "passive"))
      (node (ref "U8") (pin "3") (pinfunction "T+_3") (pintype "bidirectional"))
    )
    (net (code "10") (name "/AIN0-") (class "Default")
      (node (ref "C25") (pin "2") (pinfunction "2_2") (pintype "passive"))
      (node (ref "J4") (pin "2") (pinfunction "2_2") (pintype "passive"))
      (node (ref "U8") (pin "2") (pinfunction "T-_2") (pintype "bidirectional"))
    )
    (net (code "11") (name "/AIN1+") (class "Default")
      (node (ref "C28") (pin "1") (pinfunction "1_1") (pintype "passive"))
      (node (ref "J5") (pin "1") (pinfunction "1_1") (pintype "passive"))
      (node (ref "U7") (pin "3") (pinfunction "T+_3") (pintype "bidirectional"))
    )
    (net (code "12") (name "/AIN1-") (class "Default")
      (node (ref "C28") (pin "2") (pinfunction "2_2") (pintype "passive"))
      (node (ref "J5") (pin "2") (pinfunction "2_2") (pintype "passive"))
      (node (ref "U7") (pin "2") (pinfunction "T-_2") (pintype "bidirectional"))
    )
    (net (code "13") (name "/BT_CONN") (class "Default")
      (node (ref "R14") (pin "1") (pinfunction "1_1") (pintype "passive"))
      (node (ref "R45") (pin "2") (pinfunction "2_2") (pintype "passive"))
      (node (ref "U2") (pin "19") (pinfunction "PIO2_19") (pintype "bidirectional"))
    )
    (net (code "14") (name "/BT_RESET") (class "Default")
      (node (ref "R13") (pin "1") (pinfunction "1_1") (pintype "passive"))
      (node (ref "R44") (pin "1") (pinfunction "1_1") (pintype "passive"))
      (node (ref "U2") (pin "5") (pinfunction "RESET_5") (pintype "bidirectional"))
    )
    (net (code "15") (name "/BT_RXTX") (class "Default")
      (node (ref "R16") (pin "1") (pinfunction "1_1") (pintype "passive"))
      (node (ref "R47") (pin "2") (pinfunction "2_2") (pintype "passive"))
      (node (ref "U2") (pin "31") (pinfunction "PIO8_31") (pintype "bidirectional"))
    )
    (net (code "16") (name "/BT_STATE") (class "Default")
      (node (ref "R15") (pin "1") (pinfunction "1_1") (pintype "passive"))
      (node (ref "R46") (pin "2") (pinfunction "2_2") (pintype "passive"))
      (node (ref "U2") (pin "21") (pinfunction "PIO5_21") (pintype "bidirectional"))
    )
    (net (code "17") (name "/BT_~{RESET}") (class "Default")
      (node (ref "C3") (pin "1") (pinfunction "1_1") (pintype "passive"))
      (node (ref "R38") (pin "2") (pinfunction "2_2") (pintype "passive"))
      (node (ref "R5") (pin "1") (pinfunction "1_1") (pintype "passive"))
      (node (ref "U2") (pin "22") (pinfunction "PIO4_22") (pintype "bidirectional"))
    )
    (net (code "18") (name "/CS_AFE") (class "Default")
      (node (ref "R8") (pin "1") (pinfunction "1_1") (pintype "passive"))
      (node (ref "U4") (pin "20") (pinfunction "~{CS}_20") (pintype "input"))
    )
    (net (code "19") (name "/CS_DAC") (class "Default")
      (node (ref "R120") (pin "1") (pinfunction "1_1") (pintype "passive"))
    )
    (net (code "20") (name "/CS_SD") (class "Default")
      (node (ref "R9") (pin "1") (pinfunction "1_1") (pintype "passive"))
      (node (ref "U$1") (pin "2") (pinfunction "CS_2") (pintype "input"))
    )
    (net (code "21") (name "/CS_TC0") (class "Default")
      (node (ref "R10") (pin "1") (pinfunction "1_1") (pintype "passive"))
      (node (ref "R91") (pin "1") (pinfunction "1_1") (pintype "passive"))
    )
    (net (code "22") (name "/CS_TC1") (class "Default")
      (node (ref "R12") (pin "1") (pinfunction "1_1") (pintype "passive"))
      (node (ref "R94") (pin "1") (pinfunction "1_1") (pintype "passive"))
    )
    (net (code "23") (name "/DAC0") (class "Default")
      (node (ref "J10") (pin "S") (pinfunction "OUT_S") (pintype "bidirectional"))
      (node (ref "U9") (pin "1") (pinfunction "VOUTA_1") (pintype "output"))
    )
    (net (code "24") (name "/DAC1") (class "Default")
      (node (ref "J11") (pin "S") (pinfunction "OUT_S") (pintype "bidirectional"))
      (node (ref "U9") (pin "2") (pinfunction "VOUTB_2") (pintype "output"))
    )
    (net (code "25") (name "/DAC_~{CLR}") (class "Default")
      (node (ref "R26") (pin "2") (pinfunction "2_2") (pintype "passive"))
      (node (ref "U9") (pin "5") (pinfunction "~{CLR}_5") (pintype "input"))
    )
    (net (code "26") (name "/DAC_~{LDAC}") (class "Default")
      (node (ref "R17") (pin "1") (pinfunction "1_1") (pintype "passive"))
      (node (ref "U9") (pin "4") (pinfunction "~{LDAC}_4") (pintype "input"))
    )
    (net (code "27") (name "/LED0") (class "Default")
      (node (ref "R27") (pin "2") (pinfunction "2_2") (pintype "passive"))
      (node (ref "R98") (pin "2") (pinfunction "2_2") (pintype "passive"))
    )
    (net (code "28") (name "/LED1") (class "Default")
      (node (ref "R28") (pin "2") (pinfunction "2_2") (pintype "passive"))
      (node (ref "R99") (pin "2") (pinfunction "2_2") (pintype "passive"))
    )
    (net (code "29") (name "/MICRO_~{RESET}") (class "Default")
      (node (ref "C29") (pin "1") (pinfunction "1_1") (pintype "passive"))
      (node (ref "R1") (pin "1") (pinfunction "1_1") (pintype "passive"))
      (node (ref "R100") (pin "1") (pinfunction "1_1") (pintype "passive"))
      (node (ref "S2") (pin "P$2") (pinfunction "2_P$2") (pintype "passive"))
    )
    (net (code "30") (name "/MISO") (class "Default")
      (node (ref "R3") (pin "1") (pinfunction "1_1") (pintype "passive"))
      (node (ref "R57") (pin "2") (pinfunction "2_2") (pintype "passive"))
      (node (ref "R84") (pin "1") (pinfunction "1_1") (pintype "passive"))
      (node (ref "R92") (pin "1") (pinfunction "1_1") (pintype "passive"))
      (node (ref "R95") (pin "1") (pinfunction "1_1") (pintype "passive"))
    )
    (net (code "31") (name "/MOSI") (class "Default")
      (node (ref "R119") (pin "1") (pinfunction "1_1") (pintype "passive"))
      (node (ref "R2") (pin "1") (pinfunction "1_1") (pintype "passive"))
      (node (ref "R56") (pin "2") (pinfunction "2_2") (pintype "passive"))
      (node (ref "R85") (pin "1") (pinfunction "1_1") (pintype "passive"))
    )
    (net (code "32") (name "/RTC_SQW") (class "Default")
      (node (ref "R20") (pin "2") (pinfunction "2_2") (pintype "passive"))
      (node (ref "R76") (pin "1") (pinfunction "1_1") (pintype "passive"))
      (node (ref "U3") (pin "7") (pinfunction "SQW_7") (pintype "bidirectional"))
    )
    (net (code "33") (name "/RTC_~{INTA}") (class "Default")
      (node (ref "R21") (pin "2") (pinfunction "2_2") (pintype "passive"))
      (node (ref "R79") (pin "1") (pinfunction "1_1") (pintype "passive"))
      (node (ref "U3") (pin "3") (pinfunction "~{INTA}_3") (pintype "bidirectional"))
    )
    (net (code "34") (name "/SCK") (class "Default")
      (node (ref "R118") (pin "1") (pinfunction "1_1") (pintype "passive"))
      (node (ref "R4") (pin "1") (pinfunction "1_1") (pintype "passive"))
      (node (ref "R55") (pin "2") (pinfunction "2_2") (pintype "passive"))
      (node (ref "R86") (pin "1") (pinfunction "1_1") (pintype "passive"))
      (node (ref "R90") (pin "1") (pinfunction "1_1") (pintype "passive"))
      (node (ref "R93") (pin "1") (pinfunction "1_1") (pintype "passive"))
    )
    (net (code "35") (name "/SCL") (class "Default")
      (node (ref "R52") (pin "2") (pinfunction "2_2") (pintype "passive"))
      (node (ref "R7") (pin "1") (pinfunction "1_1") (pintype "passive"))
      (node (ref "R81") (pin "2") (pinfunction "2_2") (pintype "passive"))
    )
    (net (code "36") (name "/SDA") (class "Default")
      (node (ref "R51") (pin "2") (pinfunction "2_2") (pintype "passive"))
      (node (ref "R6") (pin "1") (pinfunction "1_1") (pintype "passive"))
      (node (ref "R82") (pin "2") (pinfunction "2_2") (pintype "passive"))
    )
    (net (code "37") (name "/SD_CD") (class "Default")
      (node (ref "R22") (pin "2") (pinfunction "2_2") (pintype "passive"))
      (node (ref "U$1") (pin "CD1") (pinfunction "CARD_DETECT_CD1") (pintype "passive"))
    )
    (net (code "38") (name "/SW2") (class "Default")
      (node (ref "C30") (pin "1") (pinfunction "1_1") (pintype "passive"))
      (node (ref "R101") (pin "1") (pinfunction "1_1") (pintype "passive"))
      (node (ref "R25") (pin "2") (pinfunction "2_2") (pintype "passive"))
      (node (ref "S3") (pin "P$2") (pinfunction "2_P$2") (pintype "passive"))
    )
    (net (code "39") (name "/UART_CTS") (class "Default")
      (node (ref "R43") (pin "1") (pinfunction "1_1") (pintype "passive"))
    )
    (net (code "40") (name "/UART_RTS") (class "Default")
      (node (ref "R42") (pin "1") (pinfunction "1_1") (pintype "passive"))
    )
    (net (code "41") (name "/UART_RX") (class "Default")
      (node (ref "R40") (pin "1") (pinfunction "1_1") (pintype "passive"))
    )
    (net (code "42") (name "/UART_TX") (class "Default")
      (node (ref "R41") (pin "1") (pinfunction "1_1") (pintype "passive"))
    )
    (net (code "43") (name "/VBATT") (class "Default")
      (node (ref "C32") (pin "2") (pinfunction "2_2") (pintype "passive"))
      (node (ref "C9") (pin "2") (pinfunction "2_2") (pintype "passive"))
      (node (ref "CN1") (pin "1") (pinfunction "2_1") (pintype "passive"))
      (node (ref "U10") (pin "P$20") (pinfunction "BATT_P$20") (pintype "power_in"))
      (node (ref "U10") (pin "P$21") (pinfunction "BATT_P$21") (pintype "power_in"))
    )
    (net (code "44") (name "/VIN") (class "Default")
      (node (ref "C31") (pin "2") (pinfunction "2_2") (pintype "passive"))
      (node (ref "C34") (pin "2") (pinfunction "2_2") (pintype "passive"))
      (node (ref "J1") (pin "PWR") (pinfunction "PWR_PWR") (pintype "bidirectional"))
      (node (ref "U10") (pin "P$2") (pinfunction "DC_P$2") (pintype "power_in"))
      (node (ref "U10") (pin "P$3") (pinfunction "DC_P$3") (pintype "power_in"))
    )
    (net (code "45") (name "/VLDO") (class "Default")
      (node (ref "C6") (pin "2") (pinfunction "2_2") (pintype "passive"))
      (node (ref "R110") (pin "2") (pinfunction "2_2") (pintype "passive"))
      (node (ref "R111") (pin "2") (pinfunction "2_2") (pintype "passive"))
      (node (ref "R112") (pin "2") (pinfunction "2_2") (pintype "passive"))
      (node (ref "R113") (pin "2") (pinfunction "2_2") (pintype "passive"))
      (node (ref "R114") (pin "2") (pinfunction "2_2") (pintype "passive"))
      (node (ref "R115") (pin "2") (pinfunction "2_2") (pintype "passive"))
      (node (ref "U10") (pin "P$17") (pinfunction "LDO_P$17") (pintype "power_in"))
    )
    (net (code "46") (name "/VREF_2V5") (class "Default")
      (node (ref "C16") (pin "1") (pinfunction "1_1") (pintype "passive"))
      (node (ref "C17") (pin "1") (pinfunction "1_1") (pintype "passive"))
      (node (ref "R73") (pin "1") (pinfunction "1_1") (pintype "passive"))
      (node (ref "U6") (pin "5") (pinfunction "VOUT_5") (pintype "bidirectional"))
    )
    (net (code "47") (name "/VSYS") (class "Default")
      (node (ref "C41") (pin "1") (pinfunction "1_1") (pintype "passive"))
      (node (ref "C42") (pin "1") (pinfunction "1_1") (pintype "passive"))
      (node (ref "C47") (pin "1") (pinfunction "1_1") (pintype "passive"))
      (node (ref "C48") (pin "1") (pinfunction "1_1") (pintype "passive"))
      (node (ref "C7") (pin "2") (pinfunction "2_2") (pintype "passive"))
      (node (ref "C8") (pin "2") (pinfunction "2_2") (pintype "passive"))
      (node (ref "R11") (pin "1") (pinfunction "1_1") (pintype "passive"))
      (node (ref "U10") (pin "P$23") (pinfunction "SYS_P$23") (pintype "power_in"))
      (node (ref "U10") (pin "P$24") (pinfunction "SYS_P$24") (pintype "power_in"))
      (node (ref "U11") (pin "4") (pinfunction "IN_4") (pintype "power_in"))
      (node (ref "U11") (pin "8") (pinfunction "~{SHDN}_8") (pintype "input"))
      (node (ref "U12") (pin "4") (pinfunction "IN_4") (pintype "power_in"))
      (node (ref "U12") (pin "8") (pinfunction "~{SHDN}_8") (pintype "input"))
    )
    (net (code "48") (name "/VUSB") (class "Default")
      (node (ref "C33") (pin "2") (pinfunction "2_2") (pintype "passive"))
      (node (ref "C35") (pin "2") (pinfunction "2_2") (pintype "passive"))
      (node (ref "U1") (pin "39") (pinfunction "P$39_39") (pintype "bidirectional"))
      (node (ref "U10") (pin "P$18") (pinfunction "USB_P$18") (pintype "power_in"))
      (node (ref "U10") (pin "P$19") (pinfunction "USB_P$19") (pintype "power_in"))
    )
    (net (code "49") (name "3.3V") (class "Default")
      (node (ref "C10") (pin "1") (pinfunction "1_1") (pintype "passive"))
      (node (ref "C12") (pin "2") (pinfunction "2_2") (pintype "passive"))
      (node (ref "C14") (pin "2") (pinfunction "2_2") (pintype "passive"))
      (node (ref "C21") (pin "2") (pinfunction "2_2") (pintype "passive"))
      (node (ref "C22") (pin "1") (pinfunction "1_1") (pintype "passive"))
      (node (ref "C23") (pin "2") (pinfunction "2_2") (pintype "passive"))
      (node (ref "C24") (pin "2") (pinfunction "2_2") (pintype "passive"))
      (node (ref "C26") (pin "2") (pinfunction "2_2") (pintype "passive"))
      (node (ref "C27") (pin "2") (pinfunction "2_2") (pintype "passive"))
      (node (ref "C4") (pin "2") (pinfunction "2_2") (pintype "passive"))
      (node (ref "C45") (pin "2") (pinfunction "2_2") (pintype "passive"))
      (node (ref "C46") (pin "2") (pinfunction "2_2") (pintype "passive"))
      (node (ref "C5") (pin "2") (pinfunction "2_2") (pintype "passive"))
      (node (ref "R100") (pin "2") (pinfunction "2_2") (pintype "passive"))
      (node (ref "R101") (pin "2") (pinfunction "2_2") (pintype "passive"))
      (node (ref "R117") (pin "1") (pinfunction "1_1") (pintype "passive"))
      (node (ref "R44") (pin "2") (pinfunction "2_2") (pintype "passive"))
      (node (ref "R49") (pin "2") (pinfunction "2_2") (pintype "passive"))
      (node (ref "R50") (pin "2") (pinfunction "2_2") (pintype "passive"))
      (node (ref "R76") (pin "2") (pinfunction "2_2") (pintype "passive"))
      (node (ref "R77") (pin "2") (pinfunction "2_2") (pintype "passive"))
      (node (ref "R78") (pin "2") (pinfunction "2_2") (pintype "passive"))
      (node (ref "R79") (pin "2") (pinfunction "2_2") (pintype "passive"))
      (node (ref "U$1") (pin "4") (pinfunction "VDD_4") (pintype "power_in"))
      (node (ref "U12") (pin "5") (pinfunction "OUT_5") (pintype "power_in"))
      (node (ref "U12") (pin "6") (pinfunction "SENSE_6") (pintype "passive"))
      (node (ref "U2") (pin "11") (pinfunction "VDD_11") (pintype "bidirectional"))
      (node (ref "U3") (pin "8") (pinfunction "VCC_8") (pintype "power_in"))
      (node (ref "U4") (pin "16") (pinfunction "DVDD_16") (pintype "power_in"))
      (node (ref "U5") (pin "5") (pinfunction "VDD_5") (pintype "power_in"))
      (node (ref "U7") (pin "4") (pinfunction "VDD_4") (pintype "bidirectional"))
      (node (ref "U8") (pin "4") (pinfunction "VDD_4") (pintype "bidirectional"))
    )
    (net (code "50") (name "5V") (class "Default")
      (node (ref "C11") (pin "2") (pinfunction "2_2") (pintype "passive"))
      (node (ref "C13") (pin "2") (pinfunction "2_2") (pintype "passive"))
      (node (ref "C15") (pin "1") (pinfunction "1_1") (pintype "passive"))
      (node (ref "C18") (pin "1") (pinfunction "1_1") (pintype "passive"))
      (node (ref "C43") (pin "2") (pinfunction "2_2") (pintype "passive"))
      (node (ref "C44") (pin "2") (pinfunction "2_2") (pintype "passive"))
      (node (ref "C49") (pin "2") (pinfunction "2_2") (pintype "passive"))
      (node (ref "C51") (pin "2") (pinfunction "2_2") (pintype "passive"))
      (node (ref "R116") (pin "1") (pinfunction "1_1") (pintype "passive"))
      (node (ref "R75") (pin "2") (pinfunction "2_2") (pintype "passive"))
      (node (ref "U11") (pin "5") (pinfunction "OUT_5") (pintype "power_in"))
      (node (ref "U11") (pin "6") (pinfunction "SENSE_6") (pintype "passive"))
      (node (ref "U4") (pin "1") (pinfunction "AVDD_1") (pintype "power_in"))
      (node (ref "U6") (pin "4") (pinfunction "VIN_4") (pintype "bidirectional"))
      (node (ref "U9") (pin "9") (pinfunction "VDD_9") (pintype "power_in"))
    )
    (net (code "51") (name "GND") (class "Default")
      (node (ref "C1") (pin "1") (pinfunction "1_1") (pintype "passive"))
      (node (ref "C10") (pin "2") (pinfunction "2_2") (pintype "passive"))
      (node (ref "C11") (pin "1") (pinfunction "1_1") (pintype "passive"))
      (node (ref "C12") (pin "1") (pinfunction "1_1") (pintype "passive"))
      (node (ref "C13") (pin "1") (pinfunction "1_1") (pintype "passive"))
      (node (ref "C14") (pin "1") (pinfunction "1_1") (pintype "passive"))
      (node (ref "C15") (pin "2") (pinfunction "2_2") (pintype "passive"))
      (node (ref "C16") (pin "2") (pinfunction "2_2") (pintype "passive"))
      (node (ref "C17") (pin "2") (pinfunction "2_2") (pintype "passive"))
      (node (ref "C18") (pin "2") (pinfunction "2_2") (pintype "passive"))
      (node (ref "C19") (pin "2") (pinfunction "2_2") (pintype "passive"))
      (node (ref "C2") (pin "1") (pinfunction "1_1") (pintype "passive"))
      (node (ref "C20") (pin "2") (pinfunction "2_2") (pintype "passive"))
      (node (ref "C21") (pin "1") (pinfunction "1_1") (pintype "passive"))
      (node (ref "C22") (pin "2") (pinfunction "2_2") (pintype "passive"))
      (node (ref "C23") (pin "1") (pinfunction "1_1") (pintype "passive"))
      (node (ref "C24") (pin "1") (pinfunction "1_1") (pintype "passive"))
      (node (ref "C26") (pin "1") (pinfunction "1_1") (pintype "passive"))
      (node (ref "C27") (pin "1") (pinfunction "1_1") (pintype "passive"))
      (node (ref "C29") (pin "2") (pinfunction "2_2") (pintype "passive"))
      (node (ref "C3") (pin "2") (pinfunction "2_2") (pintype "passive"))
      (node (ref "C30") (pin "2") (pinfunction "2_2") (pintype "passive"))
      (node (ref "C31") (pin "1") (pinfunction "1_1") (pintype "passive"))
      (node (ref "C32") (pin "1") (pinfunction "1_1") (pintype "passive"))
      (node (ref "C33") (pin "1") (pinfunction "1_1") (pintype "passive"))
      (node (ref "C34") (pin "1") (pinfunction "1_1") (pintype "passive"))
      (node (ref "C35") (pin "1") (pinfunction "1_1") (pintype "passive"))
      (node (ref "C37") (pin "2") (pinfunction "2_2") (pintype "passive"))
      (node (ref "C38") (pin "2") (pinfunction "2_2") (pintype "passive"))
      (node (ref "C39") (pin "2") (pinfunction "2_2") (pintype "passive"))
      (node (ref "C4") (pin "1") (pinfunction "1_1") (pintype "passive"))
      (node (ref "C40") (pin "2") (pinfunction "2_2") (pintype "passive"))
      (node (ref "C41") (pin "2") (pinfunction "2_2") (pintype "passive"))
      (node (ref "C42") (pin "2") (pinfunction "2_2") (pintype "passive"))
      (node (ref "C43") (pin "1") (pinfunction "1_1") (pintype "passive"))
      (node (ref "C44") (pin "1") (pinfunction "1_1") (pintype "passive"))
      (node (ref "C45") (pin "1") (pinfunction "1_1") (pintype "passive"))
      (node (ref "C46") (pin "1") (pinfunction "1_1") (pintype "passive"))
      (node (ref "C47") (pin "2") (pinfunction "2_2") (pintype "passive"))
      (node (ref "C48") (pin "2") (pinfunction "2_2") (pintype "passive"))
      (node (ref "C49") (pin "1") (pinfunction "1_1") (pintype "passive"))
      (node (ref "C5") (pin "1") (pinfunction "1_1") (pintype "passive"))
      (node (ref "C50") (pin "2") (pinfunction "2_2") (pintype "passive"))
      (node (ref "C51") (pin "1") (pinfunction "1_1") (pintype "passive"))
      (node (ref "C6") (pin "1") (pinfunction "1_1") (pintype "passive"))
      (node (ref "C7") (pin "1") (pinfunction "1_1") (pintype "passive"))
      (node (ref "C8") (pin "1") (pinfunction "1_1") (pintype "passive"))
      (node (ref "C9") (pin "1") (pinfunction "1_1") (pintype "passive"))
      (node (ref "CN1") (pin "2") (pinfunction "1_2") (pintype "passive"))
      (node (ref "D1") (pin "C") (pinfunction "C_C") (pintype "passive"))
      (node (ref "D2") (pin "C") (pinfunction "C_C") (pintype "passive"))
      (node (ref "D3") (pin "C") (pinfunction "C_C") (pintype "passive"))
      (node (ref "J1") (pin "GND") (pinfunction "GND_GND") (pintype "bidirectional"))
      (node (ref "J1") (pin "GNDBREAK") (pinfunction "GNDBREAK_GNDBREAK") (pintype "bidirectional"))
      (node (ref "J10") (pin "GND") (pinfunction "GND_GND") (pintype "bidirectional"))
      (node (ref "J11") (pin "GND") (pinfunction "GND_GND") (pintype "bidirectional"))
      (node (ref "J2") (pin "GND") (pinfunction "GND_GND") (pintype "bidirectional"))
      (node (ref "LED3") (pin "P$3") (pinfunction "GC_P$3") (pintype "passive"))
      (node (ref "LED3") (pin "P$4") (pinfunction "RC_P$4") (pintype "passive"))
      (node (ref "PAD1") (pin "1") (pinfunction "P_1") (pintype "passive"))
      (node (ref "PAD2") (pin "1") (pinfunction "P_1") (pintype "passive"))
      (node (ref "R102") (pin "1") (pinfunction "1_1") (pintype "passive"))
      (node (ref "R104") (pin "1") (pinfunction "1_1") (pintype "passive"))
      (node (ref "R105") (pin "1") (pinfunction "1_1") (pintype "passive"))
      (node (ref "R106") (pin "1") (pinfunction "1_1") (pintype "passive"))
      (node (ref "R107") (pin "1") (pinfunction "1_1") (pintype "passive"))
      (node (ref "R108") (pin "1") (pinfunction "1_1") (pintype "passive"))
      (node (ref "R109") (pin "1") (pinfunction "1_1") (pintype "passive"))
      (node (ref "R128") (pin "1") (pinfunction "1_1") (pintype "passive"))
      (node (ref "R130") (pin "1") (pinfunction "1_1") (pintype "passive"))
      (node (ref "R33") (pin "1") (pinfunction "1_1") (pintype "passive"))
      (node (ref "R34") (pin "1") (pinfunction "1_1") (pintype "passive"))
      (node (ref "R35") (pin "1") (pinfunction "1_1") (pintype "passive"))
      (node (ref "R36") (pin "1") (pinfunction "1_1") (pintype "passive"))
      (node (ref "R37") (pin "1") (pinfunction "1_1") (pintype "passive"))
      (node (ref "R38") (pin "1") (pinfunction "1_1") (pintype "passive"))
      (node (ref "R39") (pin "1") (pinfunction "1_1") (pintype "passive"))
      (node (ref "R48") (pin "1") (pinfunction "1_1") (pintype "passive"))
      (node (ref "S2") (pin "P$1") (pinfunction "1_P$1") (pintype "passive"))
      (node (ref "S3") (pin "P$1") (pinfunction "1_P$1") (pintype "passive"))
      (node (ref "U$1") (pin "6") (pinfunction "VSS_6") (pintype "power_in"))
      (node (ref "U$1") (pin "MT1") (pinfunction "GND_MT1") (pintype "power_in"))
      (node (ref "U$1") (pin "MT2") (pinfunction "GND1_MT2") (pintype "power_in"))
      (node (ref "U1") (pin "1") (pinfunction "P$1_1") (pintype "bidirectional"))
      (node (ref "U10") (pin "P$13") (pinfunction "GND_P$13") (pintype "power_in"))
      (node (ref "U10") (pin "P$29") (pinfunction "EP_P$29") (pintype "power_in"))
      (node (ref "U10") (pin "P$9") (pinfunction "GND_P$9") (pintype "power_in"))
      (node (ref "U11") (pin "3") (pinfunction "GND_3") (pintype "power_in"))
      (node (ref "U12") (pin "3") (pinfunction "GND_3") (pintype "power_in"))
      (node (ref "U2") (pin "1") (pinfunction "GND_1") (pintype "bidirectional"))
      (node (ref "U2") (pin "12") (pinfunction "GND1_12") (pintype "bidirectional"))
      (node (ref "U2") (pin "28") (pinfunction "GND2_28") (pintype "bidirectional"))
      (node (ref "U2") (pin "29") (pinfunction "GND3_29") (pintype "bidirectional"))
      (node (ref "U3") (pin "4") (pinfunction "GND_4") (pintype "power_in"))
      (node (ref "U4") (pin "17") (pinfunction "DGND_17") (pintype "power_in"))
      (node (ref "U4") (pin "2") (pinfunction "AGND_2") (pintype "power_in"))
      (node (ref "U4") (pin "3") (pinfunction "VREFN_3") (pintype "passive"))
      (node (ref "U4") (pin "5") (pinfunction "AINCOM_5") (pintype "input"))
      (node (ref "U5") (pin "2") (pinfunction "GND_2") (pintype "power_in"))
      (node (ref "U5") (pin "DAP") (pinfunction "DAP_DAP") (pintype "bidirectional"))
      (node (ref "U6") (pin "2") (pinfunction "GND_2") (pintype "bidirectional"))
      (node (ref "U7") (pin "1") (pinfunction "VSS_1") (pintype "bidirectional"))
      (node (ref "U8") (pin "1") (pinfunction "VSS_1") (pintype "bidirectional"))
      (node (ref "U9") (pin "3") (pinfunction "GND_3") (pintype "power_in"))
    )
    (net (code "52") (name "Net-(D1-PadA)") (class "Default")
      (node (ref "D1") (pin "A") (pinfunction "A_A") (pintype "passive"))
      (node (ref "R45") (pin "1") (pinfunction "1_1") (pintype "passive"))
    )
    (net (code "53") (name "Net-(D2-PadA)") (class "Default")
      (node (ref "D2") (pin "A") (pinfunction "A_A") (pintype "passive"))
      (node (ref "R46") (pin "1") (pinfunction "1_1") (pintype "passive"))
    )
    (net (code "54") (name "Net-(D3-PadA)") (class "Default")
      (node (ref "D3") (pin "A") (pinfunction "A_A") (pintype "passive"))
      (node (ref "R47") (pin "1") (pinfunction "1_1") (pintype "passive"))
    )
    (net (code "55") (name "Net-(LED3-GA)") (class "Default")
      (node (ref "LED3") (pin "P$1") (pinfunction "GA_P$1") (pintype "passive"))
      (node (ref "R99") (pin "1") (pinfunction "1_1") (pintype "passive"))
    )
    (net (code "56") (name "Net-(LED3-RA)") (class "Default")
      (node (ref "LED3") (pin "P$2") (pinfunction "RA_P$2") (pintype "passive"))
      (node (ref "R98") (pin "1") (pinfunction "1_1") (pintype "passive"))
    )
    (net (code "57") (name "Net-(U$1-DATA_IN)") (class "Default")
      (node (ref "R85") (pin "2") (pinfunction "2_2") (pintype "passive"))
      (node (ref "U$1") (pin "3") (pinfunction "DATA_IN_3") (pintype "input"))
    )
    (net (code "58") (name "Net-(U$1-DATA_OUT)") (class "Default")
      (node (ref "R84") (pin "2") (pinfunction "2_2") (pintype "passive"))
      (node (ref "U$1") (pin "7") (pinfunction "DATA_OUT_7") (pintype "output"))
    )
    (net (code "59") (name "Net-(U$1-SCLK)") (class "Default")
      (node (ref "R86") (pin "2") (pinfunction "2_2") (pintype "passive"))
      (node (ref "U$1") (pin "5") (pinfunction "SCLK_5") (pintype "input"))
    )
    (net (code "60") (name "Net-(U1-P$2)") (class "Default")
      (node (ref "C1") (pin "2") (pinfunction "2_2") (pintype "passive"))
      (node (ref "C2") (pin "2") (pinfunction "2_2") (pintype "passive"))
      (node (ref "R11") (pin "2") (pinfunction "2_2") (pintype "passive"))
      (node (ref "U1") (pin "2") (pinfunction "P$2_2") (pintype "bidirectional"))
    )
    (net (code "61") (name "Net-(U1-P$4)") (class "Default")
      (node (ref "R1") (pin "2") (pinfunction "2_2") (pintype "passive"))
      (node (ref "U1") (pin "4") (pinfunction "P$4_4") (pintype "bidirectional"))
    )
    (net (code "62") (name "Net-(U1-P$5)") (class "Default")
      (node (ref "R2") (pin "2") (pinfunction "2_2") (pintype "passive"))
      (node (ref "U1") (pin "5") (pinfunction "P$5_5") (pintype "bidirectional"))
    )
    (net (code "63") (name "Net-(U1-P$6)") (class "Default")
      (node (ref "R3") (pin "2") (pinfunction "2_2") (pintype "passive"))
      (node (ref "U1") (pin "6") (pinfunction "P$6_6") (pintype "bidirectional"))
    )
    (net (code "64") (name "Net-(U1-P$7)") (class "Default")
      (node (ref "R4") (pin "2") (pinfunction "2_2") (pintype "passive"))
      (node (ref "U1") (pin "7") (pinfunction "P$7_7") (pintype "bidirectional"))
    )
    (net (code "65") (name "Net-(U1-P$8)") (class "Default")
      (node (ref "R5") (pin "2") (pinfunction "2_2") (pintype "passive"))
      (node (ref "U1") (pin "8") (pinfunction "P$8_8") (pintype "bidirectional"))
    )
    (net (code "66") (name "Net-(U1-P$9)") (class "Default")
      (node (ref "R6") (pin "2") (pinfunction "2_2") (pintype "passive"))
      (node (ref "U1") (pin "9") (pinfunction "P$9_9") (pintype "bidirectional"))
    )
    (net (code "67") (name "Net-(U1-P$10)") (class "Default")
      (node (ref "R7") (pin "2") (pinfunction "2_2") (pintype "passive"))
      (node (ref "U1") (pin "10") (pinfunction "P$10_10") (pintype "bidirectional"))
    )
    (net (code "68") (name "Net-(U1-P$11)") (class "Default")
      (node (ref "R8") (pin "2") (pinfunction "2_2") (pintype "passive"))
      (node (ref "U1") (pin "11") (pinfunction "P$11_11") (pintype "bidirectional"))
    )
    (net (code "69") (name "Net-(U1-P$12)") (class "Default")
      (node (ref "R9") (pin "2") (pinfunction "2_2") (pintype "passive"))
      (node (ref "U1") (pin "12") (pinfunction "P$12_12") (pintype "bidirectional"))
    )
    (net (code "70") (name "Net-(U1-P$13)") (class "Default")
      (node (ref "R10") (pin "2") (pinfunction "2_2") (pintype "passive"))
      (node (ref "U1") (pin "13") (pinfunction "P$13_13") (pintype "bidirectional"))
    )
    (net (code "71") (name "Net-(U1-P$14)") (class "Default")
      (node (ref "R12") (pin "2") (pinfunction "2_2") (pintype "passive"))
      (node (ref "U1") (pin "14") (pinfunction "P$14_14") (pintype "bidirectional"))
    )
    (net (code "72") (name "Net-(U1-P$15)") (class "Default")
      (node (ref "R13") (pin "2") (pinfunction "2_2") (pintype "passive"))
      (node (ref "U1") (pin "15") (pinfunction "P$15_15") (pintype "bidirectional"))
    )
    (net (code "73") (name "Net-(U1-P$16)") (class "Default")
      (node (ref "R14") (pin "2") (pinfunction "2_2") (pintype "passive"))
      (node (ref "U1") (pin "16") (pinfunction "P$16_16") (pintype "bidirectional"))
    )
    (net (code "74") (name "Net-(U1-P$17)") (class "Default")
      (node (ref "R15") (pin "2") (pinfunction "2_2") (pintype "passive"))
      (node (ref "U1") (pin "17") (pinfunction "P$17_17") (pintype "bidirectional"))
    )
    (net (code "75") (name "Net-(U1-P$18)") (class "Default")
      (node (ref "R16") (pin "2") (pinfunction "2_2") (pintype "passive"))
      (node (ref "U1") (pin "18") (pinfunction "P$18_18") (pintype "bidirectional"))
    )
    (net (code "76") (name "Net-(U1-P$19)") (class "Default")
      (node (ref "R17") (pin "2") (pinfunction "2_2") (pintype "passive"))
      (node (ref "U1") (pin "19") (pinfunction "P$19_19") (pintype "bidirectional"))
    )
    (net (code "77") (name "Net-(U1-P$20)") (class "Default")
      (node (ref "R18") (pin "2") (pinfunction "2_2") (pintype "passive"))
      (node (ref "U1") (pin "20") (pinfunction "P$20_20") (pintype "bidirectional"))
    )
    (net (code "78") (name "Net-(U1-P$21)") (class "Default")
      (node (ref "R28") (pin "1") (pinfunction "1_1") (pintype "passive"))
      (node (ref "U1") (pin "21") (pinfunction "P$21_21") (pintype "bidirectional"))
    )
    (net (code "79") (name "Net-(U1-P$22)") (class "Default")
      (node (ref "R27") (pin "1") (pinfunction "1_1") (pintype "passive"))
      (node (ref "U1") (pin "22") (pinfunction "P$22_22") (pintype "bidirectional"))
    )
    (net (code "80") (name "Net-(U1-P$23)") (class "Default")
      (node (ref "R26") (pin "1") (pinfunction "1_1") (pintype "passive"))
      (node (ref "U1") (pin "23") (pinfunction "P$23_23") (pintype "bidirectional"))
    )
    (net (code "81") (name "Net-(U1-P$24)") (class "Default")
      (node (ref "R25") (pin "1") (pinfunction "1_1") (pintype "passive"))
      (node (ref "U1") (pin "24") (pinfunction "P$24_24") (pintype "bidirectional"))
    )
    (net (code "82") (name "Net-(U1-P$25)") (class "Default")
      (node (ref "R24") (pin "1") (pinfunction "1_1") (pintype "passive"))
      (node (ref "U1") (pin "25") (pinfunction "P$25_25") (pintype "bidirectional"))
    )
    (net (code "83") (name "Net-(U1-P$26)") (class "Default")
      (node (ref "R23") (pin "1") (pinfunction "1_1") (pintype "passive"))
      (node (ref "U1") (pin "26") (pinfunction "P$26_26") (pintype "bidirectional"))
    )
    (net (code "84") (name "Net-(U1-P$27)") (class "Default")
      (node (ref "R22") (pin "1") (pinfunction "1_1") (pintype "passive"))
      (node (ref "U1") (pin "27") (pinfunction "P$27_27") (pintype "bidirectional"))
    )
    (net (code "85") (name "Net-(U1-P$28)") (class "Default")
      (node (ref "R21") (pin "1") (pinfunction "1_1") (pintype "passive"))
      (node (ref "U1") (pin "28") (pinfunction "P$28_28") (pintype "bidirectional"))
    )
    (net (code "86") (name "Net-(U1-P$29)") (class "Default")
      (node (ref "R20") (pin "1") (pinfunction "1_1") (pintype "passive"))
      (node (ref "U1") (pin "29") (pinfunction "P$29_29") (pintype "bidirectional"))
    )
    (net (code "87") (name "Net-(U1-P$30)") (class "Default")
      (node (ref "R19") (pin "1") (pinfunction "1_1") (pintype "passive"))
      (node (ref "U1") (pin "30") (pinfunction "P$30_30") (pintype "bidirectional"))
    )
    (net (code "88") (name "Net-(U2-PIO3)") (class "Default")
      (node (ref "R39") (pin "2") (pinfunction "2_2") (pintype "passive"))
      (node (ref "U2") (pin "20") (pinfunction "PIO3_20") (pintype "bidirectional"))
    )
    (net (code "89") (name "Net-(U2-PIO6)") (class "Default")
      (node (ref "R33") (pin "2") (pinfunction "2_2") (pintype "passive"))
      (node (ref "U2") (pin "3") (pinfunction "PIO6_3") (pintype "bidirectional"))
    )
    (net (code "90") (name "Net-(U2-PIO7)") (class "Default")
      (node (ref "R34") (pin "2") (pinfunction "2_2") (pintype "passive"))
      (node (ref "U2") (pin "4") (pinfunction "PIO7_4") (pintype "bidirectional"))
    )
    (net (code "91") (name "Net-(U2-PIO9)") (class "Default")
      (node (ref "R35") (pin "2") (pinfunction "2_2") (pintype "passive"))
      (node (ref "U2") (pin "32") (pinfunction "PIO9_32") (pintype "bidirectional"))
    )
    (net (code "92") (name "Net-(U2-PIO10)") (class "Default")
      (node (ref "R36") (pin "2") (pinfunction "2_2") (pintype "passive"))
      (node (ref "U2") (pin "33") (pinfunction "PIO10_33") (pintype "bidirectional"))
    )
    (net (code "93") (name "Net-(U2-PIO11)") (class "Default")
      (node (ref "R37") (pin "2") (pinfunction "2_2") (pintype "passive"))
      (node (ref "U2") (pin "34") (pinfunction "PIO11_34") (pintype "bidirectional"))
    )
    (net (code "94") (name "Net-(U2-UARTCTS)") (class "Default")
      (node (ref "R43") (pin "2") (pinfunction "2_2") (pintype "passive"))
      (node (ref "U2") (pin "16") (pinfunction "UARTCTS_16") (pintype "bidirectional"))
    )
    (net (code "95") (name "Net-(U2-UARTRTS)") (class "Default")
      (node (ref "R42") (pin "2") (pinfunction "2_2") (pintype "passive"))
      (node (ref "U2") (pin "15") (pinfunction "UARTRTS_15") (pintype "bidirectional"))
    )
    (net (code "96") (name "Net-(U2-UARTRX)") (class "Default")
      (node (ref "R40") (pin "2") (pinfunction "2_2") (pintype "passive"))
      (node (ref "U2") (pin "13") (pinfunction "UARTRX_13") (pintype "bidirectional"))
    )
    (net (code "97") (name "Net-(U2-UARTTX)") (class "Default")
      (node (ref "R41") (pin "2") (pinfunction "2_2") (pintype "passive"))
      (node (ref "U2") (pin "14") (pinfunction "UARTTX_14") (pintype "bidirectional"))
    )
    (net (code "98") (name "Net-(U3-SCL)") (class "Default")
      (node (ref "R77") (pin "1") (pinfunction "1_1") (pintype "passive"))
      (node (ref "R81") (pin "1") (pinfunction "1_1") (pintype "passive"))
      (node (ref "U3") (pin "6") (pinfunction "SCL_6") (pintype "bidirectional"))
    )
    (net (code "99") (name "Net-(U3-SDA)") (class "Default")
      (node (ref "R78") (pin "1") (pinfunction "1_1") (pintype "passive"))
      (node (ref "R82") (pin "1") (pinfunction "1_1") (pintype "passive"))
      (node (ref "U3") (pin "5") (pinfunction "SDA_5") (pintype "bidirectional"))
    )
    (net (code "100") (name "Net-(U3-X1)") (class "Default")
      (node (ref "U3") (pin "1") (pinfunction "X1_1") (pintype "passive"))
      (node (ref "Y2") (pin "2") (pinfunction "2_2") (pintype "passive"))
    )
    (net (code "101") (name "Net-(U3-X2)") (class "Default")
      (node (ref "U3") (pin "2") (pinfunction "X2_2") (pintype "passive"))
      (node (ref "Y2") (pin "1") (pinfunction "1_1") (pintype "passive"))
    )
    (net (code "102") (name "Net-(U4-DIN)") (class "Default")
      (node (ref "R56") (pin "1") (pinfunction "1_1") (pintype "passive"))
      (node (ref "U4") (pin "23") (pinfunction "DIN_23") (pintype "bidirectional"))
    )
    (net (code "103") (name "Net-(U4-DOUT)") (class "Default")
      (node (ref "R57") (pin "1") (pinfunction "1_1") (pintype "passive"))
      (node (ref "U4") (pin "22") (pinfunction "DOUT_22") (pintype "output"))
    )
    (net (code "104") (name "Net-(U4-SCLK)") (class "Default")
      (node (ref "R55") (pin "1") (pinfunction "1_1") (pintype "passive"))
      (node (ref "U4") (pin "24") (pinfunction "SCLK_24") (pintype "bidirectional"))
    )
    (net (code "105") (name "Net-(U4-VREFP)") (class "Default")
      (node (ref "R73") (pin "2") (pinfunction "2_2") (pintype "passive"))
      (node (ref "U4") (pin "4") (pinfunction "VREFP_4") (pintype "passive"))
    )
    (net (code "106") (name "Net-(U4-XTAL1{slash}CLKIN)") (class "Default")
      (node (ref "C19") (pin "1") (pinfunction "1_1") (pintype "passive"))
      (node (ref "U4") (pin "19") (pinfunction "XTAL1/CLKIN_19") (pintype "input"))
      (node (ref "Y1") (pin "2") (pinfunction "2_2") (pintype "passive"))
    )
    (net (code "107") (name "Net-(U4-XTAL2)") (class "Default")
      (node (ref "C20") (pin "1") (pinfunction "1_1") (pintype "passive"))
      (node (ref "U4") (pin "18") (pinfunction "XTAL2_18") (pintype "input"))
      (node (ref "Y1") (pin "1") (pinfunction "1_1") (pintype "passive"))
    )
    (net (code "108") (name "Net-(U5-SCL)") (class "Default")
      (node (ref "R50") (pin "1") (pinfunction "1_1") (pintype "passive"))
      (node (ref "R52") (pin "1") (pinfunction "1_1") (pintype "passive"))
      (node (ref "U5") (pin "6") (pinfunction "SCL_6") (pintype "bidirectional"))
    )
    (net (code "109") (name "Net-(U5-SDA)") (class "Default")
      (node (ref "R49") (pin "1") (pinfunction "1_1") (pintype "passive"))
      (node (ref "R51") (pin "1") (pinfunction "1_1") (pintype "passive"))
      (node (ref "U5") (pin "1") (pinfunction "SDA_1") (pintype "bidirectional"))
    )
    (net (code "110") (name "Net-(U6-EN)") (class "Default")
      (node (ref "R75") (pin "1") (pinfunction "1_1") (pintype "passive"))
      (node (ref "U6") (pin "3") (pinfunction "EN_3") (pintype "bidirectional"))
    )
    (net (code "111") (name "Net-(U7-CS)") (class "Default")
      (node (ref "R94") (pin "2") (pinfunction "2_2") (pintype "passive"))
      (node (ref "U7") (pin "6") (pinfunction "CS_6") (pintype "bidirectional"))
    )
    (net (code "112") (name "Net-(U7-MISO)") (class "Default")
      (node (ref "R95") (pin "2") (pinfunction "2_2") (pintype "passive"))
      (node (ref "U7") (pin "7") (pinfunction "MISO_7") (pintype "bidirectional"))
    )
    (net (code "113") (name "Net-(U7-SCK)") (class "Default")
      (node (ref "R93") (pin "2") (pinfunction "2_2") (pintype "passive"))
      (node (ref "U7") (pin "5") (pinfunction "SCK_5") (pintype "bidirectional"))
    )
    (net (code "114") (name "Net-(U8-CS)") (class "Default")
      (node (ref "R91") (pin "2") (pinfunction "2_2") (pintype "passive"))
      (node (ref "U8") (pin "6") (pinfunction "CS_6") (pintype "bidirectional"))
    )
    (net (code "115") (name "Net-(U8-MISO)") (class "Default")
      (node (ref "R92") (pin "2") (pinfunction "2_2") (pintype "passive"))
      (node (ref "U8") (pin "7") (pinfunction "MISO_7") (pintype "bidirectional"))
    )
    (net (code "116") (name "Net-(U8-SCK)") (class "Default")
      (node (ref "R90") (pin "2") (pinfunction "2_2") (pintype "passive"))
      (node (ref "U8") (pin "5") (pinfunction "SCK_5") (pintype "bidirectional"))
    )
    (net (code "117") (name "Net-(U9-DIN)") (class "Default")
      (node (ref "R119") (pin "2") (pinfunction "2_2") (pintype "passive"))
      (node (ref "U9") (pin "8") (pinfunction "DIN_8") (pintype "input"))
    )
    (net (code "118") (name "Net-(U9-SCLK)") (class "Default")
      (node (ref "R118") (pin "2") (pinfunction "2_2") (pintype "passive"))
      (node (ref "U9") (pin "7") (pinfunction "SCLK_7") (pintype "bidirectional"))
    )
    (net (code "119") (name "Net-(U9-VREF_IO)") (class "Default")
      (node (ref "C50") (pin "1") (pinfunction "1_1") (pintype "passive"))
      (node (ref "U9") (pin "10") (pinfunction "VREF_IO_10") (pintype "bidirectional"))
    )
    (net (code "120") (name "Net-(U9-~{SYNC})") (class "Default")
      (node (ref "R120") (pin "2") (pinfunction "2_2") (pintype "passive"))
      (node (ref "U9") (pin "6") (pinfunction "~{SYNC}_6") (pintype "input"))
    )
    (net (code "121") (name "Net-(U10-CT)") (class "Default")
      (node (ref "C37") (pin "1") (pinfunction "1_1") (pintype "passive"))
      (node (ref "U10") (pin "P$10") (pinfunction "CT_P$10") (pintype "passive"))
    )
    (net (code "122") (name "Net-(U10-ISET)") (class "Default")
      (node (ref "R48") (pin "2") (pinfunction "2_2") (pintype "passive"))
      (node (ref "U10") (pin "P$11") (pinfunction "ISET_P$11") (pintype "passive"))
    )
    (net (code "123") (name "Net-(U10-PEN1)") (class "Default")
      (node (ref "R107") (pin "2") (pinfunction "2_2") (pintype "passive"))
      (node (ref "U10") (pin "P$5") (pinfunction "PEN1_P$5") (pintype "input"))
    )
    (net (code "124") (name "Net-(U10-PEN2)") (class "Default")
      (node (ref "R108") (pin "2") (pinfunction "2_2") (pintype "passive"))
      (node (ref "U10") (pin "P$6") (pinfunction "PEN2_P$6") (pintype "input"))
    )
    (net (code "125") (name "Net-(U10-PSET)") (class "Default")
      (node (ref "R102") (pin "2") (pinfunction "2_2") (pintype "passive"))
      (node (ref "U10") (pin "P$7") (pinfunction "PSET_P$7") (pintype "passive"))
    )
    (net (code "126") (name "Net-(U10-THM)") (class "Default")
      (node (ref "R103") (pin "1") (pinfunction "1_1") (pintype "passive"))
      (node (ref "R104") (pin "2") (pinfunction "2_2") (pintype "passive"))
      (node (ref "U10") (pin "P$14") (pinfunction "THM_P$14") (pintype "passive"))
    )
    (net (code "127") (name "Net-(U10-THMEN)") (class "Default")
      (node (ref "R105") (pin "2") (pinfunction "2_2") (pintype "passive"))
      (node (ref "U10") (pin "P$15") (pinfunction "THMEN_P$15") (pintype "input"))
    )
    (net (code "128") (name "Net-(U10-THMSW)") (class "Default")
      (node (ref "R103") (pin "2") (pinfunction "2_2") (pintype "passive"))
      (node (ref "U10") (pin "P$16") (pinfunction "THMSW_P$16") (pintype "passive"))
    )
    (net (code "129") (name "Net-(U10-USUS)") (class "Default")
      (node (ref "R106") (pin "2") (pinfunction "2_2") (pintype "passive"))
      (node (ref "U10") (pin "P$12") (pinfunction "USUS_P$12") (pintype "input"))
    )
    (net (code "130") (name "Net-(U10-VL)") (class "Default")
      (node (ref "C38") (pin "1") (pinfunction "1_1") (pintype "passive"))
      (node (ref "U10") (pin "P$8") (pinfunction "VL_P$8") (pintype "passive"))
    )
    (net (code "131") (name "Net-(U10-~{CEN})") (class "Default")
      (node (ref "R109") (pin "2") (pinfunction "2_2") (pintype "passive"))
      (node (ref "U10") (pin "P$4") (pinfunction "~{CEN}_P$4") (pintype "input"))
    )
    (net (code "132") (name "Net-(U10-~{CHG})") (class "Default")
      (node (ref "R110") (pin "1") (pinfunction "1_1") (pintype "passive"))
      (node (ref "U10") (pin "P$22") (pinfunction "~{CHG}_P$22") (pintype "output"))
    )
    (net (code "133") (name "Net-(U10-~{DOK})") (class "Default")
      (node (ref "R115") (pin "1") (pinfunction "1_1") (pintype "passive"))
      (node (ref "U10") (pin "P$26") (pinfunction "~{DOK}_P$26") (pintype "output"))
    )
    (net (code "134") (name "Net-(U10-~{DONE})") (class "Default")
      (node (ref "R111") (pin "1") (pinfunction "1_1") (pintype "passive"))
      (node (ref "U10") (pin "P$1") (pinfunction "~{DONE}_P$1") (pintype "output"))
    )
    (net (code "135") (name "Net-(U10-~{FLT})") (class "Default")
      (node (ref "R113") (pin "1") (pinfunction "1_1") (pintype "passive"))
      (node (ref "U10") (pin "P$28") (pinfunction "~{FLT}_P$28") (pintype "output"))
    )
    (net (code "136") (name "Net-(U10-~{OT})") (class "Default")
      (node (ref "R112") (pin "1") (pinfunction "1_1") (pintype "passive"))
      (node (ref "U10") (pin "P$25") (pinfunction "~{OT}_P$25") (pintype "output"))
    )
    (net (code "137") (name "Net-(U10-~{UOK})") (class "Default")
      (node (ref "R114") (pin "1") (pinfunction "1_1") (pintype "passive"))
      (node (ref "U10") (pin "P$27") (pinfunction "~{UOK}_P$27") (pintype "output"))
    )
    (net (code "138") (name "Net-(U11-BYPASS)") (class "Default")
      (node (ref "C40") (pin "1") (pinfunction "1_1") (pintype "passive"))
      (node (ref "U11") (pin "1") (pinfunction "BYPASS_1") (pintype "passive"))
    )
    (net (code "139") (name "Net-(U11-~{ERR})") (class "Default")
      (node (ref "R116") (pin "2") (pinfunction "2_2") (pintype "passive"))
      (node (ref "U11") (pin "7") (pinfunction "~{ERR}_7") (pintype "output"))
    )
    (net (code "140") (name "Net-(U12-BYPASS)") (class "Default")
      (node (ref "C39") (pin "1") (pinfunction "1_1") (pintype "passive"))
      (node (ref "U12") (pin "1") (pinfunction "BYPASS_1") (pintype "passive"))
    )
    (net (code "141") (name "Net-(U12-~{ERR})") (class "Default")
      (node (ref "R117") (pin "2") (pinfunction "2_2") (pintype "passive"))
      (node (ref "U12") (pin "7") (pinfunction "~{ERR}_7") (pintype "output"))
    )
    (net (code "142") (name "unconnected-(J2-PadD+)") (class "Default")
      (node (ref "J2") (pin "D+") (pinfunction "D+_D+") (pintype "bidirectional"))
    )
    (net (code "143") (name "unconnected-(J2-PadD-)") (class "Default")
      (node (ref "J2") (pin "D-") (pinfunction "D-_D-") (pintype "bidirectional"))
    )
    (net (code "144") (name "unconnected-(J2-PadVBUS)") (class "Default")
      (node (ref "J2") (pin "VBUS") (pinfunction "VBUS_VBUS") (pintype "bidirectional"))
    )
    (net (code "145") (name "unconnected-(R24-Pad2)") (class "Default")
      (node (ref "R24") (pin "2") (pinfunction "2_2") (pintype "passive"))
    )
    (net (code "146") (name "unconnected-(U$1-CARD_DETECT1-PadCD2)") (class "Default")
      (node (ref "U$1") (pin "CD2") (pinfunction "CARD_DETECT1_CD2") (pintype "passive"))
    )
    (net (code "147") (name "unconnected-(U$1-DAT1-Pad8)") (class "Default")
      (node (ref "U$1") (pin "8") (pinfunction "DAT1_8") (pintype "bidirectional"))
    )
    (net (code "148") (name "unconnected-(U$1-DAT2-Pad1)") (class "Default")
      (node (ref "U$1") (pin "1") (pinfunction "DAT2_1") (pintype "bidirectional"))
    )
    (net (code "149") (name "unconnected-(U1-P$3-Pad3)") (class "Default")
      (node (ref "U1") (pin "3") (pinfunction "P$3_3") (pintype "bidirectional"))
    )
    (net (code "150") (name "unconnected-(U1-P$31-Pad31)") (class "Default")
      (node (ref "U1") (pin "31") (pinfunction "P$31_31") (pintype "bidirectional"))
    )
    (net (code "151") (name "unconnected-(U1-P$32-Pad32)") (class "Default")
      (node (ref "U1") (pin "32") (pinfunction "P$32_32") (pintype "bidirectional"))
    )
    (net (code "152") (name "unconnected-(U1-P$33-Pad33)") (class "Default")
      (node (ref "U1") (pin "33") (pinfunction "P$33_33") (pintype "bidirectional"))
    )
    (net (code "153") (name "unconnected-(U1-P$34-Pad34)") (class "Default")
      (node (ref "U1") (pin "34") (pinfunction "P$34_34") (pintype "bidirectional"))
    )
    (net (code "154") (name "unconnected-(U1-P$35-Pad35)") (class "Default")
      (node (ref "U1") (pin "35") (pinfunction "P$35_35") (pintype "bidirectional"))
    )
    (net (code "155") (name "unconnected-(U1-P$36-Pad36)") (class "Default")
      (node (ref "U1") (pin "36") (pinfunction "P$36_36") (pintype "bidirectional"))
    )
    (net (code "156") (name "unconnected-(U1-P$37-Pad37)") (class "Default")
      (node (ref "U1") (pin "37") (pinfunction "P$37_37") (pintype "bidirectional"))
    )
    (net (code "157") (name "unconnected-(U1-P$38-Pad38)") (class "Default")
      (node (ref "U1") (pin "38") (pinfunction "P$38_38") (pintype "bidirectional"))
    )
    (net (code "158") (name "unconnected-(U1-P$40-Pad40)") (class "Default")
      (node (ref "U1") (pin "40") (pinfunction "P$40_40") (pintype "bidirectional"))
    )
    (net (code "159") (name "unconnected-(U2-AIO0-Pad30)") (class "Default")
      (node (ref "U2") (pin "30") (pinfunction "AIO0_30") (pintype "bidirectional"))
    )
    (net (code "160") (name "unconnected-(U2-AIO1-Pad35)") (class "Default")
      (node (ref "U2") (pin "35") (pinfunction "AIO1_35") (pintype "bidirectional"))
    )
    (net (code "161") (name "unconnected-(U2-PCMCLK-Pad7)") (class "Default")
      (node (ref "U2") (pin "7") (pinfunction "PCMCLK_7") (pintype "bidirectional"))
    )
    (net (code "162") (name "unconnected-(U2-PCMIN-Pad9)") (class "Default")
      (node (ref "U2") (pin "9") (pinfunction "PCMIN_9") (pintype "bidirectional"))
    )
    (net (code "163") (name "unconnected-(U2-PCMOUT-Pad10)") (class "Default")
      (node (ref "U2") (pin "10") (pinfunction "PCMOUT_10") (pintype "bidirectional"))
    )
    (net (code "164") (name "unconnected-(U2-PCMSYNC-Pad8)") (class "Default")
      (node (ref "U2") (pin "8") (pinfunction "PCMSYNC_8") (pintype "bidirectional"))
    )
    (net (code "165") (name "unconnected-(U2-SPICLK-Pad6)") (class "Default")
      (node (ref "U2") (pin "6") (pinfunction "SPICLK_6") (pintype "bidirectional"))
    )
    (net (code "166") (name "unconnected-(U2-SPICSB-Pad23)") (class "Default")
      (node (ref "U2") (pin "23") (pinfunction "SPICSB_23") (pintype "bidirectional"))
    )
    (net (code "167") (name "unconnected-(U2-SPIMISO-Pad24)") (class "Default")
      (node (ref "U2") (pin "24") (pinfunction "SPIMISO_24") (pintype "bidirectional"))
    )
    (net (code "168") (name "unconnected-(U2-SPIMOSI-Pad2)") (class "Default")
      (node (ref "U2") (pin "2") (pinfunction "SPIMOSI_2") (pintype "bidirectional"))
    )
    (net (code "169") (name "unconnected-(U2-USBD+-Pad17)") (class "Default")
      (node (ref "U2") (pin "17") (pinfunction "USBD+_17") (pintype "bidirectional"))
    )
    (net (code "170") (name "unconnected-(U2-USBD--Pad18)") (class "Default")
      (node (ref "U2") (pin "18") (pinfunction "USBD-_18") (pintype "bidirectional"))
    )
    (net (code "171") (name "unconnected-(U4-AIN4-Pad10)") (class "Default")
      (node (ref "U4") (pin "10") (pinfunction "AIN4_10") (pintype "input"))
    )
    (net (code "172") (name "unconnected-(U4-AIN5-Pad11)") (class "Default")
      (node (ref "U4") (pin "11") (pinfunction "AIN5_11") (pintype "input"))
    )
    (net (code "173") (name "unconnected-(U4-AIN6-Pad12)") (class "Default")
      (node (ref "U4") (pin "12") (pinfunction "AIN6_12") (pintype "input"))
    )
    (net (code "174") (name "unconnected-(U4-AIN7-Pad13)") (class "Default")
      (node (ref "U4") (pin "13") (pinfunction "AIN7_13") (pintype "input"))
    )
    (net (code "175") (name "unconnected-(U4-D0{slash}CLKOUT-Pad25)") (class "Default")
      (node (ref "U4") (pin "25") (pinfunction "D0/CLKOUT_25") (pintype "bidirectional"))
    )
    (net (code "176") (name "unconnected-(U4-D1-Pad26)") (class "Default")
      (node (ref "U4") (pin "26") (pinfunction "D1_26") (pintype "bidirectional"))
    )
    (net (code "177") (name "unconnected-(U4-D2-Pad27)") (class "Default")
      (node (ref "U4") (pin "27") (pinfunction "D2_27") (pintype "bidirectional"))
    )
    (net (code "178") (name "unconnected-(U4-D3-Pad28)") (class "Default")
      (node (ref "U4") (pin "28") (pinfunction "D3_28") (pintype "bidirectional"))
    )
    (net (code "179") (name "unconnected-(U5-NC3-Pad3)") (class "Default")
      (node (ref "U5") (pin "3") (pinfunction "NC3_3") (pintype "no_connect"))
    )
    (net (code "180") (name "unconnected-(U5-NC4-Pad4)") (class "Default")
      (node (ref "U5") (pin "4") (pinfunction "NC4_4") (pintype "no_connect"))
    )
    (net (code "181") (name "unconnected-(U11-NC-Pad2)") (class "Default")
      (node (ref "U11") (pin "2") (pinfunction "NC_2") (pintype "bidirectional"))
    )
    (net (code "182") (name "unconnected-(U12-NC-Pad2)") (class "Default")
      (node (ref "U12") (pin "2") (pinfunction "NC_2") (pintype "bidirectional"))
    )
  )
)
